# relay_isolation_circuit.net
KiCad netlist of a schematic drawn in Altium Designer
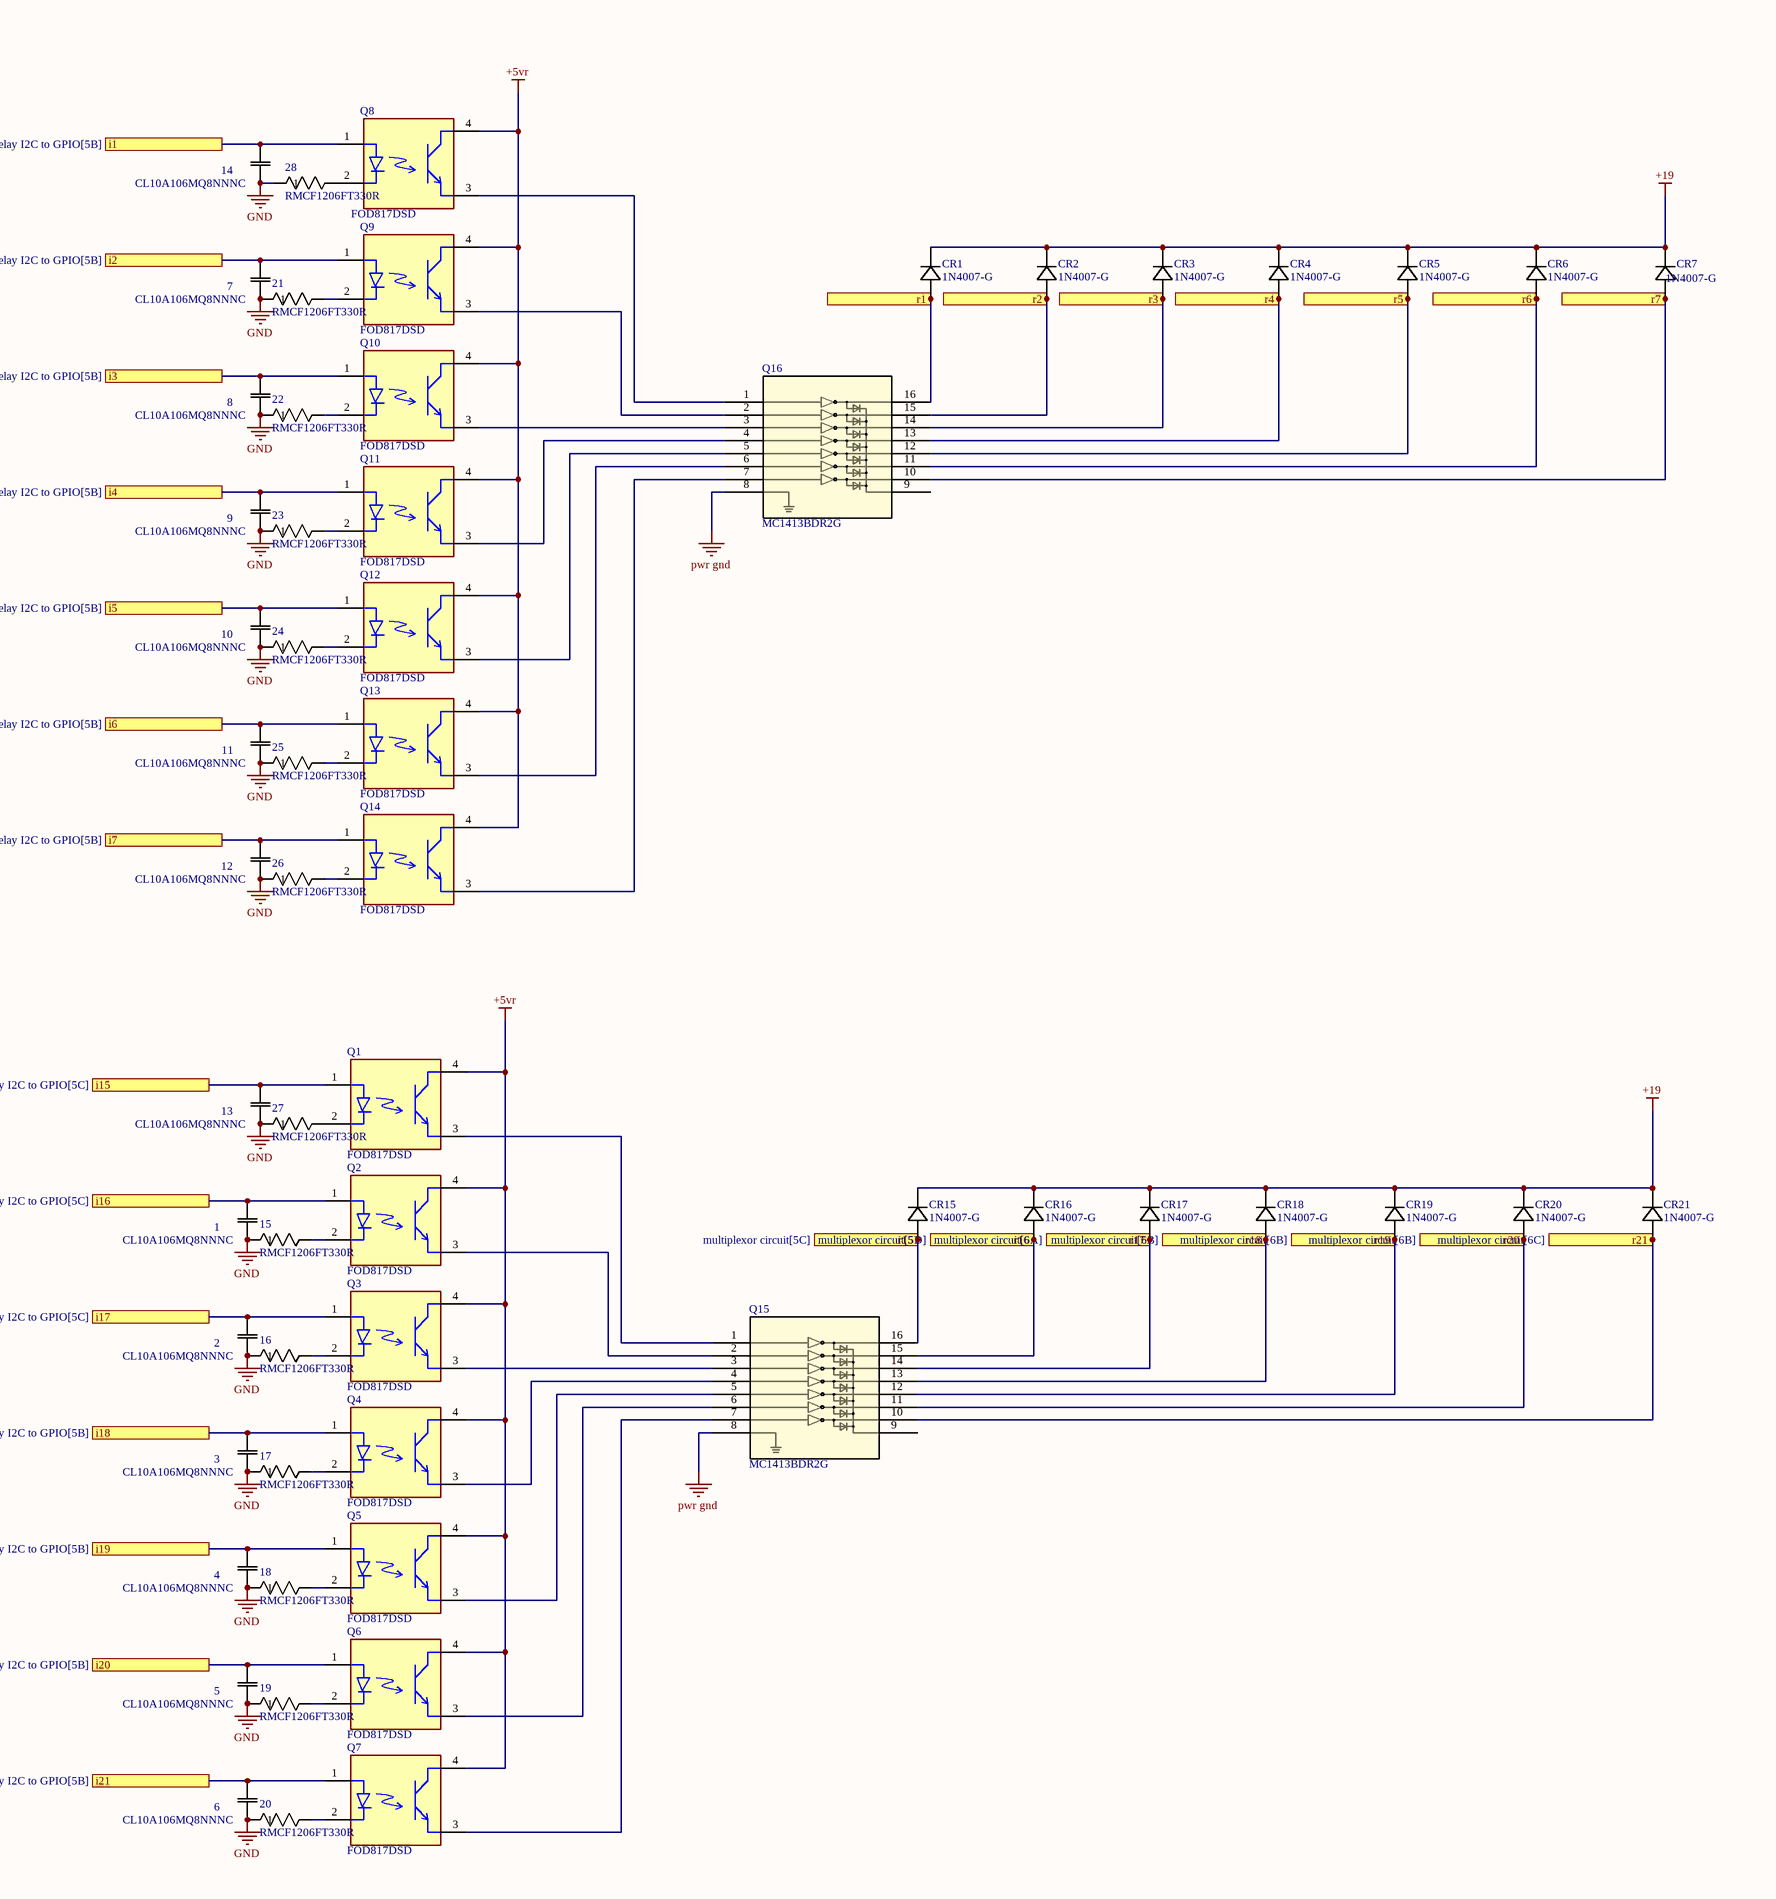
[diagram p0: relay isolation circuit.SchDoc, left]
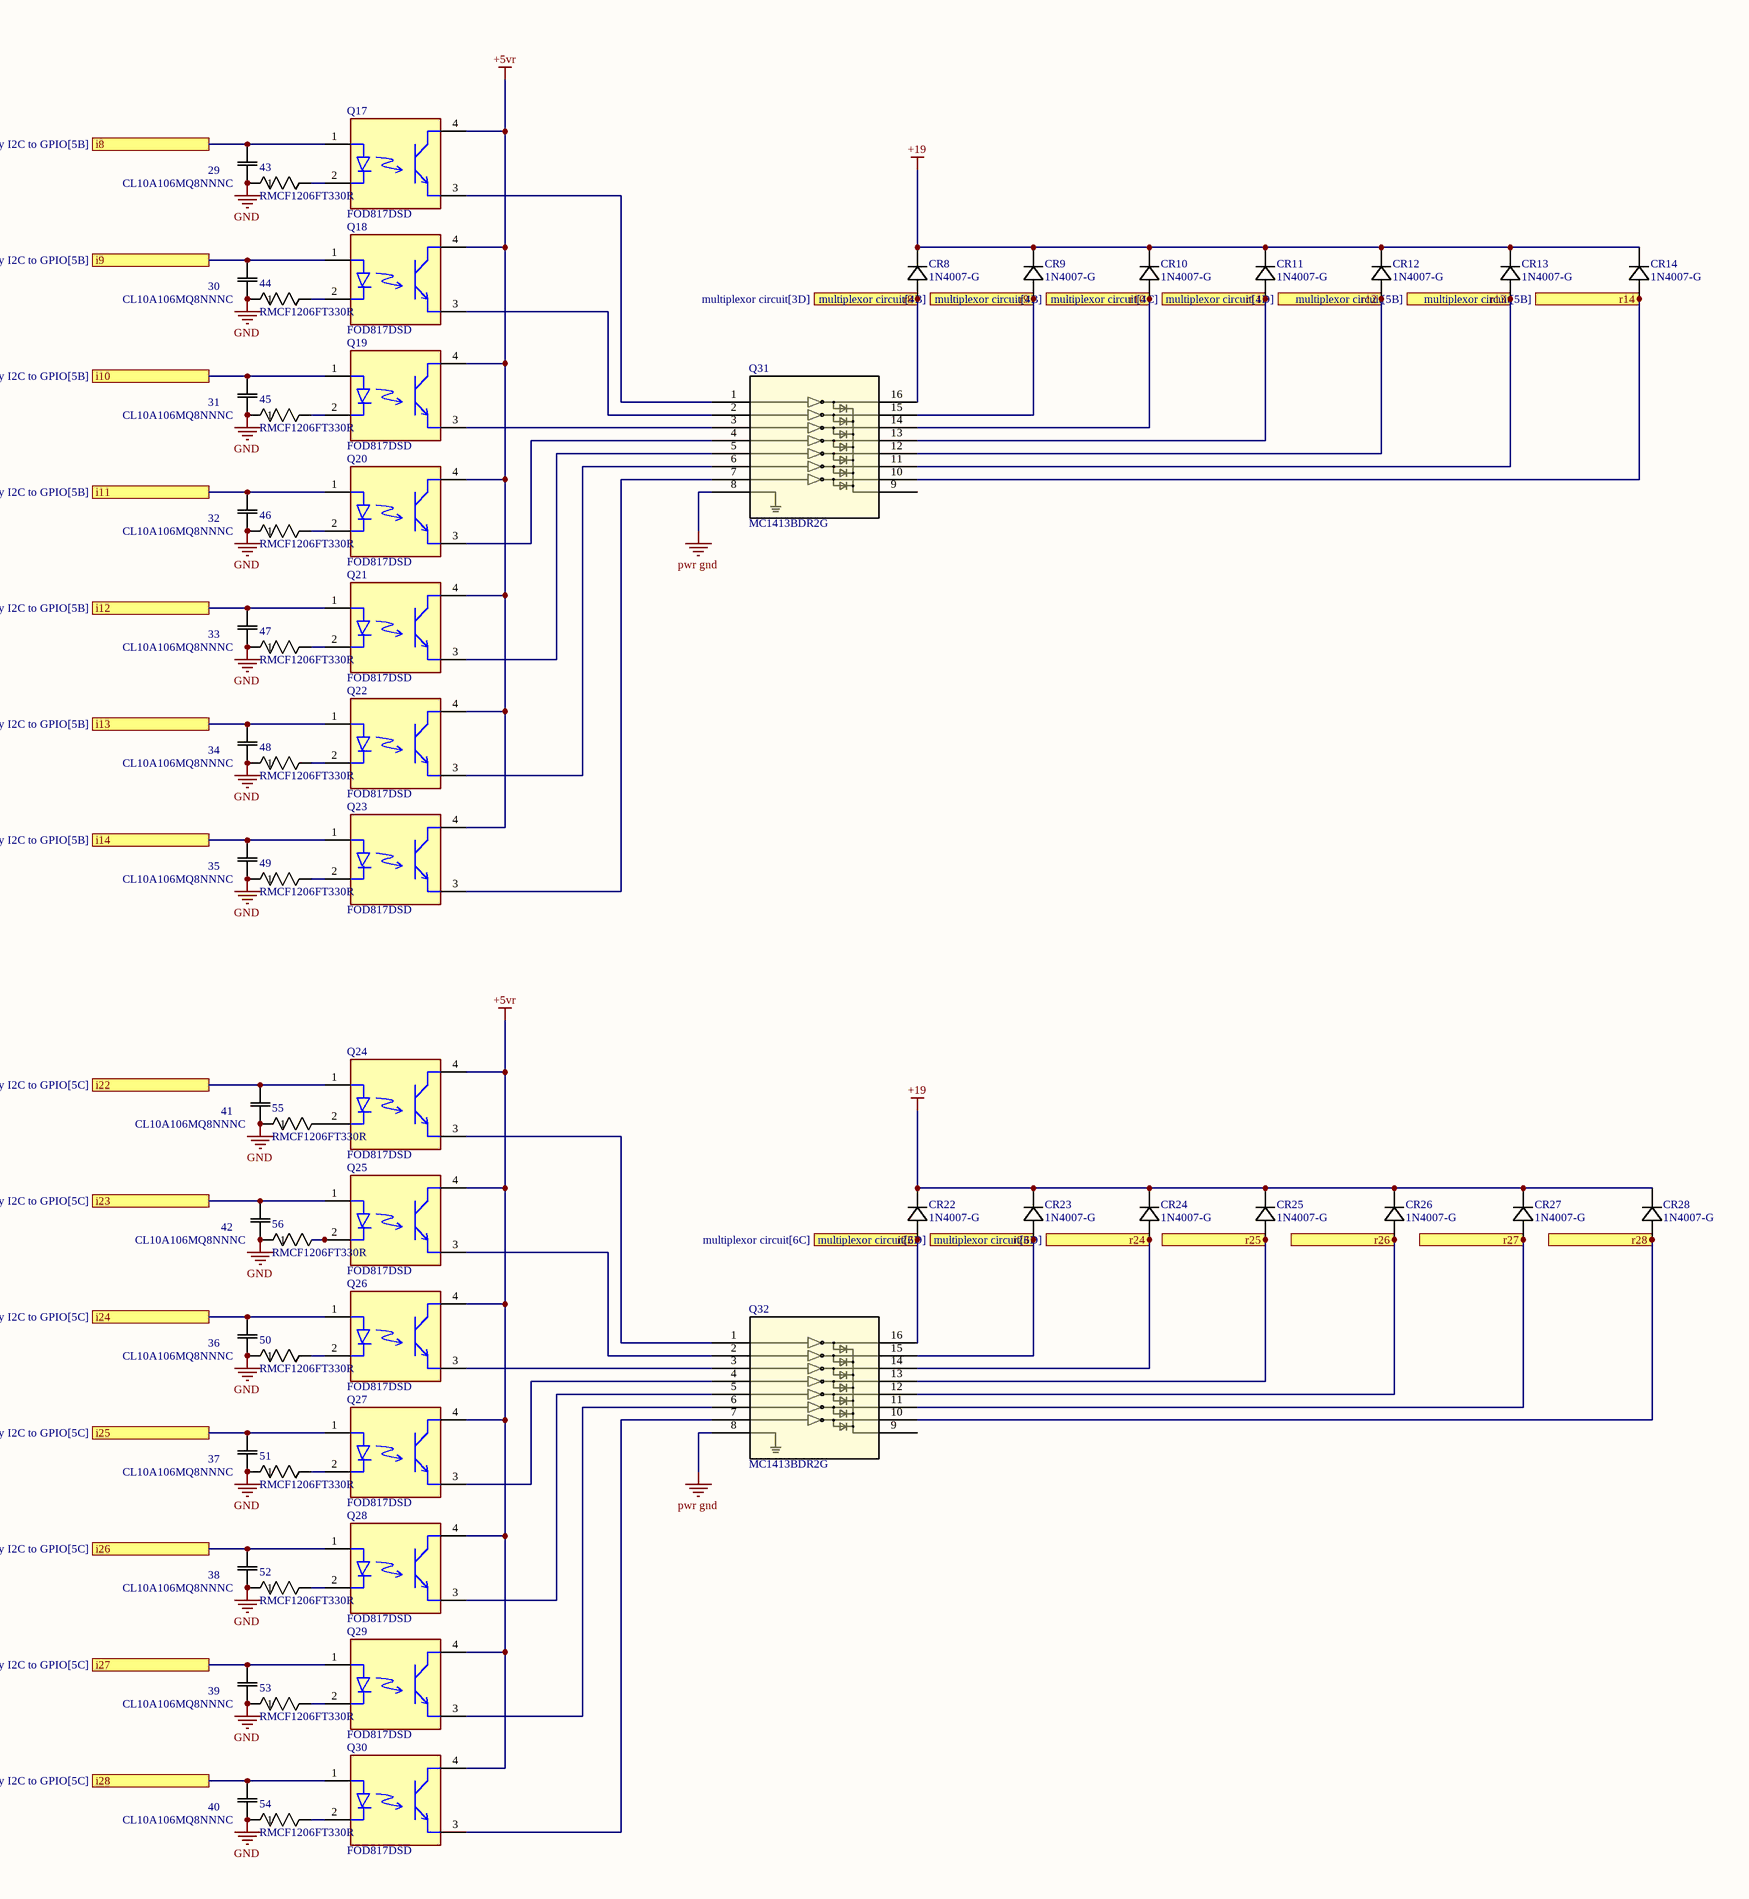
[diagram p1: relay isolation circuit.SchDoc, right]

(export (version "E")
  (design (tool "Eeschema 10.0.6"))
  (components
    (comp (ref "1")
      (value "CL10A106MQ8NNNC")
      (footprint "CAP_CL10_SAM")
      (description "No Description Available")
      (fields (field (name "COPYRIGHT") "Copyright (C) 2022 Ultra Librarian. All rights reserved."))
      (libsource (lib "CL10A106MQ8NNNC") (part "CL10A106MQ8NNNC"))
    )
    (comp (ref "2")
      (value "CL10A106MQ8NNNC")
      (footprint "CAP_CL10_SAM")
      (description "No Description Available")
      (fields (field (name "COPYRIGHT") "Copyright (C) 2022 Ultra Librarian. All rights reserved."))
      (libsource (lib "CL10A106MQ8NNNC") (part "CL10A106MQ8NNNC"))
    )
    (comp (ref "3")
      (value "CL10A106MQ8NNNC")
      (footprint "CAP_CL10_SAM")
      (description "No Description Available")
      (fields (field (name "COPYRIGHT") "Copyright (C) 2022 Ultra Librarian. All rights reserved."))
      (libsource (lib "CL10A106MQ8NNNC") (part "CL10A106MQ8NNNC"))
    )
    (comp (ref "4")
      (value "CL10A106MQ8NNNC")
      (footprint "CAP_CL10_SAM")
      (description "No Description Available")
      (fields (field (name "COPYRIGHT") "Copyright (C) 2022 Ultra Librarian. All rights reserved."))
      (libsource (lib "CL10A106MQ8NNNC") (part "CL10A106MQ8NNNC"))
    )
    (comp (ref "5")
      (value "CL10A106MQ8NNNC")
      (footprint "CAP_CL10_SAM")
      (description "No Description Available")
      (fields (field (name "COPYRIGHT") "Copyright (C) 2022 Ultra Librarian. All rights reserved."))
      (libsource (lib "CL10A106MQ8NNNC") (part "CL10A106MQ8NNNC"))
    )
    (comp (ref "6")
      (value "CL10A106MQ8NNNC")
      (footprint "CAP_CL10_SAM")
      (description "No Description Available")
      (fields (field (name "COPYRIGHT") "Copyright (C) 2022 Ultra Librarian. All rights reserved."))
      (libsource (lib "CL10A106MQ8NNNC") (part "CL10A106MQ8NNNC"))
    )
    (comp (ref "7")
      (value "CL10A106MQ8NNNC")
      (footprint "CAP_CL10_SAM")
      (description "No Description Available")
      (fields (field (name "COPYRIGHT") "Copyright (C) 2022 Ultra Librarian. All rights reserved."))
      (libsource (lib "CL10A106MQ8NNNC") (part "CL10A106MQ8NNNC"))
    )
    (comp (ref "8")
      (value "CL10A106MQ8NNNC")
      (footprint "CAP_CL10_SAM")
      (description "No Description Available")
      (fields (field (name "COPYRIGHT") "Copyright (C) 2022 Ultra Librarian. All rights reserved."))
      (libsource (lib "CL10A106MQ8NNNC") (part "CL10A106MQ8NNNC"))
    )
    (comp (ref "9")
      (value "CL10A106MQ8NNNC")
      (footprint "CAP_CL10_SAM")
      (description "No Description Available")
      (fields (field (name "COPYRIGHT") "Copyright (C) 2022 Ultra Librarian. All rights reserved."))
      (libsource (lib "CL10A106MQ8NNNC") (part "CL10A106MQ8NNNC"))
    )
    (comp (ref "10")
      (value "CL10A106MQ8NNNC")
      (footprint "CAP_CL10_SAM")
      (description "No Description Available")
      (fields (field (name "COPYRIGHT") "Copyright (C) 2022 Ultra Librarian. All rights reserved."))
      (libsource (lib "CL10A106MQ8NNNC") (part "CL10A106MQ8NNNC"))
    )
    (comp (ref "11")
      (value "CL10A106MQ8NNNC")
      (footprint "CAP_CL10_SAM")
      (description "No Description Available")
      (fields (field (name "COPYRIGHT") "Copyright (C) 2022 Ultra Librarian. All rights reserved."))
      (libsource (lib "CL10A106MQ8NNNC") (part "CL10A106MQ8NNNC"))
    )
    (comp (ref "12")
      (value "CL10A106MQ8NNNC")
      (footprint "CAP_CL10_SAM")
      (description "No Description Available")
      (fields (field (name "COPYRIGHT") "Copyright (C) 2022 Ultra Librarian. All rights reserved."))
      (libsource (lib "CL10A106MQ8NNNC") (part "CL10A106MQ8NNNC"))
    )
    (comp (ref "13")
      (value "CL10A106MQ8NNNC")
      (footprint "CAP_CL10_SAM")
      (description "No Description Available")
      (fields (field (name "COPYRIGHT") "Copyright (C) 2022 Ultra Librarian. All rights reserved."))
      (libsource (lib "CL10A106MQ8NNNC") (part "CL10A106MQ8NNNC"))
    )
    (comp (ref "14")
      (value "CL10A106MQ8NNNC")
      (footprint "CAP_CL10_SAM")
      (description "No Description Available")
      (fields (field (name "COPYRIGHT") "Copyright (C) 2022 Ultra Librarian. All rights reserved."))
      (libsource (lib "CL10A106MQ8NNNC") (part "CL10A106MQ8NNNC"))
    )
    (comp (ref "15")
      (value "RMCF1206FT330R")
      (footprint "STA_RMCF1206_STP")
      (description "No Description Available")
      (fields (field (name "COPYRIGHT") "Copyright (C) 2022 Ultra Librarian. All rights reserved."))
      (libsource (lib "RMCF1206FT330R") (part "RMCF1206FT330R"))
    )
    (comp (ref "16")
      (value "RMCF1206FT330R")
      (footprint "STA_RMCF1206_STP")
      (description "No Description Available")
      (fields (field (name "COPYRIGHT") "Copyright (C) 2022 Ultra Librarian. All rights reserved."))
      (libsource (lib "RMCF1206FT330R") (part "RMCF1206FT330R"))
    )
    (comp (ref "17")
      (value "RMCF1206FT330R")
      (footprint "STA_RMCF1206_STP")
      (description "No Description Available")
      (fields (field (name "COPYRIGHT") "Copyright (C) 2022 Ultra Librarian. All rights reserved."))
      (libsource (lib "RMCF1206FT330R") (part "RMCF1206FT330R"))
    )
    (comp (ref "18")
      (value "RMCF1206FT330R")
      (footprint "STA_RMCF1206_STP")
      (description "No Description Available")
      (fields (field (name "COPYRIGHT") "Copyright (C) 2022 Ultra Librarian. All rights reserved."))
      (libsource (lib "RMCF1206FT330R") (part "RMCF1206FT330R"))
    )
    (comp (ref "19")
      (value "RMCF1206FT330R")
      (footprint "STA_RMCF1206_STP")
      (description "No Description Available")
      (fields (field (name "COPYRIGHT") "Copyright (C) 2022 Ultra Librarian. All rights reserved."))
      (libsource (lib "RMCF1206FT330R") (part "RMCF1206FT330R"))
    )
    (comp (ref "20")
      (value "RMCF1206FT330R")
      (footprint "STA_RMCF1206_STP")
      (description "No Description Available")
      (fields (field (name "COPYRIGHT") "Copyright (C) 2022 Ultra Librarian. All rights reserved."))
      (libsource (lib "RMCF1206FT330R") (part "RMCF1206FT330R"))
    )
    (comp (ref "21")
      (value "RMCF1206FT330R")
      (footprint "STA_RMCF1206_STP")
      (description "No Description Available")
      (fields (field (name "COPYRIGHT") "Copyright (C) 2022 Ultra Librarian. All rights reserved."))
      (libsource (lib "RMCF1206FT330R") (part "RMCF1206FT330R"))
    )
    (comp (ref "22")
      (value "RMCF1206FT330R")
      (footprint "STA_RMCF1206_STP")
      (description "No Description Available")
      (fields (field (name "COPYRIGHT") "Copyright (C) 2022 Ultra Librarian. All rights reserved."))
      (libsource (lib "RMCF1206FT330R") (part "RMCF1206FT330R"))
    )
    (comp (ref "23")
      (value "RMCF1206FT330R")
      (footprint "STA_RMCF1206_STP")
      (description "No Description Available")
      (fields (field (name "COPYRIGHT") "Copyright (C) 2022 Ultra Librarian. All rights reserved."))
      (libsource (lib "RMCF1206FT330R") (part "RMCF1206FT330R"))
    )
    (comp (ref "24")
      (value "RMCF1206FT330R")
      (footprint "STA_RMCF1206_STP")
      (description "No Description Available")
      (fields (field (name "COPYRIGHT") "Copyright (C) 2022 Ultra Librarian. All rights reserved."))
      (libsource (lib "RMCF1206FT330R") (part "RMCF1206FT330R"))
    )
    (comp (ref "25")
      (value "RMCF1206FT330R")
      (footprint "STA_RMCF1206_STP")
      (description "No Description Available")
      (fields (field (name "COPYRIGHT") "Copyright (C) 2022 Ultra Librarian. All rights reserved."))
      (libsource (lib "RMCF1206FT330R") (part "RMCF1206FT330R"))
    )
    (comp (ref "26")
      (value "RMCF1206FT330R")
      (footprint "STA_RMCF1206_STP")
      (description "No Description Available")
      (fields (field (name "COPYRIGHT") "Copyright (C) 2022 Ultra Librarian. All rights reserved."))
      (libsource (lib "RMCF1206FT330R") (part "RMCF1206FT330R"))
    )
    (comp (ref "27")
      (value "RMCF1206FT330R")
      (footprint "STA_RMCF1206_STP")
      (description "No Description Available")
      (fields (field (name "COPYRIGHT") "Copyright (C) 2022 Ultra Librarian. All rights reserved."))
      (libsource (lib "RMCF1206FT330R") (part "RMCF1206FT330R"))
    )
    (comp (ref "28")
      (value "RMCF1206FT330R")
      (footprint "STA_RMCF1206_STP")
      (description "No Description Available")
      (fields (field (name "COPYRIGHT") "Copyright (C) 2022 Ultra Librarian. All rights reserved."))
      (libsource (lib "RMCF1206FT330R") (part "RMCF1206FT330R"))
    )
    (comp (ref "29")
      (value "CL10A106MQ8NNNC")
      (footprint "CAP_CL10_SAM")
      (description "No Description Available")
      (fields (field (name "COPYRIGHT") "Copyright (C) 2022 Ultra Librarian. All rights reserved."))
      (libsource (lib "CL10A106MQ8NNNC") (part "CL10A106MQ8NNNC"))
    )
    (comp (ref "30")
      (value "CL10A106MQ8NNNC")
      (footprint "CAP_CL10_SAM")
      (description "No Description Available")
      (fields (field (name "COPYRIGHT") "Copyright (C) 2022 Ultra Librarian. All rights reserved."))
      (libsource (lib "CL10A106MQ8NNNC") (part "CL10A106MQ8NNNC"))
    )
    (comp (ref "31")
      (value "CL10A106MQ8NNNC")
      (footprint "CAP_CL10_SAM")
      (description "No Description Available")
      (fields (field (name "COPYRIGHT") "Copyright (C) 2022 Ultra Librarian. All rights reserved."))
      (libsource (lib "CL10A106MQ8NNNC") (part "CL10A106MQ8NNNC"))
    )
    (comp (ref "32")
      (value "CL10A106MQ8NNNC")
      (footprint "CAP_CL10_SAM")
      (description "No Description Available")
      (fields (field (name "COPYRIGHT") "Copyright (C) 2022 Ultra Librarian. All rights reserved."))
      (libsource (lib "CL10A106MQ8NNNC") (part "CL10A106MQ8NNNC"))
    )
    (comp (ref "33")
      (value "CL10A106MQ8NNNC")
      (footprint "CAP_CL10_SAM")
      (description "No Description Available")
      (fields (field (name "COPYRIGHT") "Copyright (C) 2022 Ultra Librarian. All rights reserved."))
      (libsource (lib "CL10A106MQ8NNNC") (part "CL10A106MQ8NNNC"))
    )
    (comp (ref "34")
      (value "CL10A106MQ8NNNC")
      (footprint "CAP_CL10_SAM")
      (description "No Description Available")
      (fields (field (name "COPYRIGHT") "Copyright (C) 2022 Ultra Librarian. All rights reserved."))
      (libsource (lib "CL10A106MQ8NNNC") (part "CL10A106MQ8NNNC"))
    )
    (comp (ref "35")
      (value "CL10A106MQ8NNNC")
      (footprint "CAP_CL10_SAM")
      (description "No Description Available")
      (fields (field (name "COPYRIGHT") "Copyright (C) 2022 Ultra Librarian. All rights reserved."))
      (libsource (lib "CL10A106MQ8NNNC") (part "CL10A106MQ8NNNC"))
    )
    (comp (ref "36")
      (value "CL10A106MQ8NNNC")
      (footprint "CAP_CL10_SAM")
      (description "No Description Available")
      (fields (field (name "COPYRIGHT") "Copyright (C) 2022 Ultra Librarian. All rights reserved."))
      (libsource (lib "CL10A106MQ8NNNC") (part "CL10A106MQ8NNNC"))
    )
    (comp (ref "37")
      (value "CL10A106MQ8NNNC")
      (footprint "CAP_CL10_SAM")
      (description "No Description Available")
      (fields (field (name "COPYRIGHT") "Copyright (C) 2022 Ultra Librarian. All rights reserved."))
      (libsource (lib "CL10A106MQ8NNNC") (part "CL10A106MQ8NNNC"))
    )
    (comp (ref "38")
      (value "CL10A106MQ8NNNC")
      (footprint "CAP_CL10_SAM")
      (description "No Description Available")
      (fields (field (name "COPYRIGHT") "Copyright (C) 2022 Ultra Librarian. All rights reserved."))
      (libsource (lib "CL10A106MQ8NNNC") (part "CL10A106MQ8NNNC"))
    )
    (comp (ref "39")
      (value "CL10A106MQ8NNNC")
      (footprint "CAP_CL10_SAM")
      (description "No Description Available")
      (fields (field (name "COPYRIGHT") "Copyright (C) 2022 Ultra Librarian. All rights reserved."))
      (libsource (lib "CL10A106MQ8NNNC") (part "CL10A106MQ8NNNC"))
    )
    (comp (ref "40")
      (value "CL10A106MQ8NNNC")
      (footprint "CAP_CL10_SAM")
      (description "No Description Available")
      (fields (field (name "COPYRIGHT") "Copyright (C) 2022 Ultra Librarian. All rights reserved."))
      (libsource (lib "CL10A106MQ8NNNC") (part "CL10A106MQ8NNNC"))
    )
    (comp (ref "41")
      (value "CL10A106MQ8NNNC")
      (footprint "CAP_CL10_SAM")
      (description "No Description Available")
      (fields (field (name "COPYRIGHT") "Copyright (C) 2022 Ultra Librarian. All rights reserved."))
      (libsource (lib "CL10A106MQ8NNNC") (part "CL10A106MQ8NNNC"))
    )
    (comp (ref "42")
      (value "CL10A106MQ8NNNC")
      (footprint "CAP_CL10_SAM")
      (description "No Description Available")
      (fields (field (name "COPYRIGHT") "Copyright (C) 2022 Ultra Librarian. All rights reserved."))
      (libsource (lib "CL10A106MQ8NNNC") (part "CL10A106MQ8NNNC"))
    )
    (comp (ref "43")
      (value "RMCF1206FT330R")
      (footprint "STA_RMCF1206_STP")
      (description "No Description Available")
      (fields (field (name "COPYRIGHT") "Copyright (C) 2022 Ultra Librarian. All rights reserved."))
      (libsource (lib "RMCF1206FT330R") (part "RMCF1206FT330R"))
    )
    (comp (ref "44")
      (value "RMCF1206FT330R")
      (footprint "STA_RMCF1206_STP")
      (description "No Description Available")
      (fields (field (name "COPYRIGHT") "Copyright (C) 2022 Ultra Librarian. All rights reserved."))
      (libsource (lib "RMCF1206FT330R") (part "RMCF1206FT330R"))
    )
    (comp (ref "45")
      (value "RMCF1206FT330R")
      (footprint "STA_RMCF1206_STP")
      (description "No Description Available")
      (fields (field (name "COPYRIGHT") "Copyright (C) 2022 Ultra Librarian. All rights reserved."))
      (libsource (lib "RMCF1206FT330R") (part "RMCF1206FT330R"))
    )
    (comp (ref "46")
      (value "RMCF1206FT330R")
      (footprint "STA_RMCF1206_STP")
      (description "No Description Available")
      (fields (field (name "COPYRIGHT") "Copyright (C) 2022 Ultra Librarian. All rights reserved."))
      (libsource (lib "RMCF1206FT330R") (part "RMCF1206FT330R"))
    )
    (comp (ref "47")
      (value "RMCF1206FT330R")
      (footprint "STA_RMCF1206_STP")
      (description "No Description Available")
      (fields (field (name "COPYRIGHT") "Copyright (C) 2022 Ultra Librarian. All rights reserved."))
      (libsource (lib "RMCF1206FT330R") (part "RMCF1206FT330R"))
    )
    (comp (ref "48")
      (value "RMCF1206FT330R")
      (footprint "STA_RMCF1206_STP")
      (description "No Description Available")
      (fields (field (name "COPYRIGHT") "Copyright (C) 2022 Ultra Librarian. All rights reserved."))
      (libsource (lib "RMCF1206FT330R") (part "RMCF1206FT330R"))
    )
    (comp (ref "49")
      (value "RMCF1206FT330R")
      (footprint "STA_RMCF1206_STP")
      (description "No Description Available")
      (fields (field (name "COPYRIGHT") "Copyright (C) 2022 Ultra Librarian. All rights reserved."))
      (libsource (lib "RMCF1206FT330R") (part "RMCF1206FT330R"))
    )
    (comp (ref "50")
      (value "RMCF1206FT330R")
      (footprint "STA_RMCF1206_STP")
      (description "No Description Available")
      (fields (field (name "COPYRIGHT") "Copyright (C) 2022 Ultra Librarian. All rights reserved."))
      (libsource (lib "RMCF1206FT330R") (part "RMCF1206FT330R"))
    )
    (comp (ref "51")
      (value "RMCF1206FT330R")
      (footprint "STA_RMCF1206_STP")
      (description "No Description Available")
      (fields (field (name "COPYRIGHT") "Copyright (C) 2022 Ultra Librarian. All rights reserved."))
      (libsource (lib "RMCF1206FT330R") (part "RMCF1206FT330R"))
    )
    (comp (ref "52")
      (value "RMCF1206FT330R")
      (footprint "STA_RMCF1206_STP")
      (description "No Description Available")
      (fields (field (name "COPYRIGHT") "Copyright (C) 2022 Ultra Librarian. All rights reserved."))
      (libsource (lib "RMCF1206FT330R") (part "RMCF1206FT330R"))
    )
    (comp (ref "53")
      (value "RMCF1206FT330R")
      (footprint "STA_RMCF1206_STP")
      (description "No Description Available")
      (fields (field (name "COPYRIGHT") "Copyright (C) 2022 Ultra Librarian. All rights reserved."))
      (libsource (lib "RMCF1206FT330R") (part "RMCF1206FT330R"))
    )
    (comp (ref "54")
      (value "RMCF1206FT330R")
      (footprint "STA_RMCF1206_STP")
      (description "No Description Available")
      (fields (field (name "COPYRIGHT") "Copyright (C) 2022 Ultra Librarian. All rights reserved."))
      (libsource (lib "RMCF1206FT330R") (part "RMCF1206FT330R"))
    )
    (comp (ref "55")
      (value "RMCF1206FT330R")
      (footprint "STA_RMCF1206_STP")
      (description "No Description Available")
      (fields (field (name "COPYRIGHT") "Copyright (C) 2022 Ultra Librarian. All rights reserved."))
      (libsource (lib "RMCF1206FT330R") (part "RMCF1206FT330R"))
    )
    (comp (ref "56")
      (value "RMCF1206FT330R")
      (footprint "STA_RMCF1206_STP")
      (description "No Description Available")
      (fields (field (name "COPYRIGHT") "Copyright (C) 2022 Ultra Librarian. All rights reserved."))
      (libsource (lib "RMCF1206FT330R") (part "RMCF1206FT330R"))
    )
    (comp (ref "CR1")
      (value "1N4007-G")
      (footprint "1N4-G")
      (description "No Description Available")
      (fields (field (name "COPYRIGHT") "Copyright (C) 2022 Ultra Librarian. All rights reserved."))
      (libsource (lib "multiplexorparts") (part "1N4007-G"))
    )
    (comp (ref "CR2")
      (value "1N4007-G")
      (footprint "1N4-G")
      (description "No Description Available")
      (fields (field (name "COPYRIGHT") "Copyright (C) 2022 Ultra Librarian. All rights reserved."))
      (libsource (lib "multiplexorparts") (part "1N4007-G"))
    )
    (comp (ref "CR3")
      (value "1N4007-G")
      (footprint "1N4-G")
      (description "No Description Available")
      (fields (field (name "COPYRIGHT") "Copyright (C) 2022 Ultra Librarian. All rights reserved."))
      (libsource (lib "multiplexorparts") (part "1N4007-G"))
    )
    (comp (ref "CR4")
      (value "1N4007-G")
      (footprint "1N4-G")
      (description "No Description Available")
      (fields (field (name "COPYRIGHT") "Copyright (C) 2022 Ultra Librarian. All rights reserved."))
      (libsource (lib "multiplexorparts") (part "1N4007-G"))
    )
    (comp (ref "CR5")
      (value "1N4007-G")
      (footprint "1N4-G")
      (description "No Description Available")
      (fields (field (name "COPYRIGHT") "Copyright (C) 2022 Ultra Librarian. All rights reserved."))
      (libsource (lib "multiplexorparts") (part "1N4007-G"))
    )
    (comp (ref "CR6")
      (value "1N4007-G")
      (footprint "1N4-G")
      (description "No Description Available")
      (fields (field (name "COPYRIGHT") "Copyright (C) 2022 Ultra Librarian. All rights reserved."))
      (libsource (lib "multiplexorparts") (part "1N4007-G"))
    )
    (comp (ref "CR7")
      (value "1N4007-G")
      (footprint "1N4-G")
      (description "No Description Available")
      (fields (field (name "COPYRIGHT") "Copyright (C) 2022 Ultra Librarian. All rights reserved."))
      (libsource (lib "multiplexorparts") (part "1N4007-G"))
    )
    (comp (ref "CR8")
      (value "1N4007-G")
      (footprint "1N4-G")
      (description "No Description Available")
      (fields (field (name "COPYRIGHT") "Copyright (C) 2022 Ultra Librarian. All rights reserved."))
      (libsource (lib "multiplexorparts") (part "1N4007-G"))
    )
    (comp (ref "CR9")
      (value "1N4007-G")
      (footprint "1N4-G")
      (description "No Description Available")
      (fields (field (name "COPYRIGHT") "Copyright (C) 2022 Ultra Librarian. All rights reserved."))
      (libsource (lib "multiplexorparts") (part "1N4007-G"))
    )
    (comp (ref "CR10")
      (value "1N4007-G")
      (footprint "1N4-G")
      (description "No Description Available")
      (fields (field (name "COPYRIGHT") "Copyright (C) 2022 Ultra Librarian. All rights reserved."))
      (libsource (lib "multiplexorparts") (part "1N4007-G"))
    )
    (comp (ref "CR11")
      (value "1N4007-G")
      (footprint "1N4-G")
      (description "No Description Available")
      (fields (field (name "COPYRIGHT") "Copyright (C) 2022 Ultra Librarian. All rights reserved."))
      (libsource (lib "multiplexorparts") (part "1N4007-G"))
    )
    (comp (ref "CR12")
      (value "1N4007-G")
      (footprint "1N4-G")
      (description "No Description Available")
      (fields (field (name "COPYRIGHT") "Copyright (C) 2022 Ultra Librarian. All rights reserved."))
      (libsource (lib "multiplexorparts") (part "1N4007-G"))
    )
    (comp (ref "CR13")
      (value "1N4007-G")
      (footprint "1N4-G")
      (description "No Description Available")
      (fields (field (name "COPYRIGHT") "Copyright (C) 2022 Ultra Librarian. All rights reserved."))
      (libsource (lib "multiplexorparts") (part "1N4007-G"))
    )
    (comp (ref "CR14")
      (value "1N4007-G")
      (footprint "1N4-G")
      (description "No Description Available")
      (fields (field (name "COPYRIGHT") "Copyright (C) 2022 Ultra Librarian. All rights reserved."))
      (libsource (lib "multiplexorparts") (part "1N4007-G"))
    )
    (comp (ref "CR15")
      (value "1N4007-G")
      (footprint "1N4-G")
      (description "No Description Available")
      (fields (field (name "COPYRIGHT") "Copyright (C) 2022 Ultra Librarian. All rights reserved."))
      (libsource (lib "multiplexorparts") (part "1N4007-G"))
    )
    (comp (ref "CR16")
      (value "1N4007-G")
      (footprint "1N4-G")
      (description "No Description Available")
      (fields (field (name "COPYRIGHT") "Copyright (C) 2022 Ultra Librarian. All rights reserved."))
      (libsource (lib "multiplexorparts") (part "1N4007-G"))
    )
    (comp (ref "CR17")
      (value "1N4007-G")
      (footprint "1N4-G")
      (description "No Description Available")
      (fields (field (name "COPYRIGHT") "Copyright (C) 2022 Ultra Librarian. All rights reserved."))
      (libsource (lib "multiplexorparts") (part "1N4007-G"))
    )
    (comp (ref "CR18")
      (value "1N4007-G")
      (footprint "1N4-G")
      (description "No Description Available")
      (fields (field (name "COPYRIGHT") "Copyright (C) 2022 Ultra Librarian. All rights reserved."))
      (libsource (lib "multiplexorparts") (part "1N4007-G"))
    )
    (comp (ref "CR19")
      (value "1N4007-G")
      (footprint "1N4-G")
      (description "No Description Available")
      (fields (field (name "COPYRIGHT") "Copyright (C) 2022 Ultra Librarian. All rights reserved."))
      (libsource (lib "multiplexorparts") (part "1N4007-G"))
    )
    (comp (ref "CR20")
      (value "1N4007-G")
      (footprint "1N4-G")
      (description "No Description Available")
      (fields (field (name "COPYRIGHT") "Copyright (C) 2022 Ultra Librarian. All rights reserved."))
      (libsource (lib "multiplexorparts") (part "1N4007-G"))
    )
    (comp (ref "CR21")
      (value "1N4007-G")
      (footprint "1N4-G")
      (description "No Description Available")
      (fields (field (name "COPYRIGHT") "Copyright (C) 2022 Ultra Librarian. All rights reserved."))
      (libsource (lib "multiplexorparts") (part "1N4007-G"))
    )
    (comp (ref "CR22")
      (value "1N4007-G")
      (footprint "1N4-G")
      (description "No Description Available")
      (fields (field (name "COPYRIGHT") "Copyright (C) 2022 Ultra Librarian. All rights reserved."))
      (libsource (lib "multiplexorparts") (part "1N4007-G"))
    )
    (comp (ref "CR23")
      (value "1N4007-G")
      (footprint "1N4-G")
      (description "No Description Available")
      (fields (field (name "COPYRIGHT") "Copyright (C) 2022 Ultra Librarian. All rights reserved."))
      (libsource (lib "multiplexorparts") (part "1N4007-G"))
    )
    (comp (ref "CR24")
      (value "1N4007-G")
      (footprint "1N4-G")
      (description "No Description Available")
      (fields (field (name "COPYRIGHT") "Copyright (C) 2022 Ultra Librarian. All rights reserved."))
      (libsource (lib "multiplexorparts") (part "1N4007-G"))
    )
    (comp (ref "CR25")
      (value "1N4007-G")
      (footprint "1N4-G")
      (description "No Description Available")
      (fields (field (name "COPYRIGHT") "Copyright (C) 2022 Ultra Librarian. All rights reserved."))
      (libsource (lib "multiplexorparts") (part "1N4007-G"))
    )
    (comp (ref "CR26")
      (value "1N4007-G")
      (footprint "1N4-G")
      (description "No Description Available")
      (fields (field (name "COPYRIGHT") "Copyright (C) 2022 Ultra Librarian. All rights reserved."))
      (libsource (lib "multiplexorparts") (part "1N4007-G"))
    )
    (comp (ref "CR27")
      (value "1N4007-G")
      (footprint "1N4-G")
      (description "No Description Available")
      (fields (field (name "COPYRIGHT") "Copyright (C) 2022 Ultra Librarian. All rights reserved."))
      (libsource (lib "multiplexorparts") (part "1N4007-G"))
    )
    (comp (ref "CR28")
      (value "1N4007-G")
      (footprint "1N4-G")
      (description "No Description Available")
      (fields (field (name "COPYRIGHT") "Copyright (C) 2022 Ultra Librarian. All rights reserved."))
      (libsource (lib "multiplexorparts") (part "1N4007-G"))
    )
    (comp (ref "Q1")
      (value "FOD817DSD")
      (footprint "FP-709AH-MFG")
      (description "OPTOISOLATOR 5KV TRANSISTOR 4SMD")
      (fields
        (field (name "MANUFACTURER") "ON Semiconductor")
        (field (name "OCTOPART") "https://octopart.com/fod817dsd-on+semiconductor-84327554")
      )
      (libsource (lib "Altium Content Vault") (part "d722738cb024cbb2b7d208cd16f279d"))
    )
    (comp (ref "Q2")
      (value "FOD817DSD")
      (footprint "FP-709AH-MFG")
      (description "OPTOISOLATOR 5KV TRANSISTOR 4SMD")
      (fields
        (field (name "MANUFACTURER") "ON Semiconductor")
        (field (name "OCTOPART") "https://octopart.com/fod817dsd-on+semiconductor-84327554")
      )
      (libsource (lib "Altium Content Vault") (part "d722738cb024cbb2b7d208cd16f279d"))
    )
    (comp (ref "Q3")
      (value "FOD817DSD")
      (footprint "FP-709AH-MFG")
      (description "OPTOISOLATOR 5KV TRANSISTOR 4SMD")
      (fields
        (field (name "MANUFACTURER") "ON Semiconductor")
        (field (name "OCTOPART") "https://octopart.com/fod817dsd-on+semiconductor-84327554")
      )
      (libsource (lib "Altium Content Vault") (part "d722738cb024cbb2b7d208cd16f279d"))
    )
    (comp (ref "Q4")
      (value "FOD817DSD")
      (footprint "FP-709AH-MFG")
      (description "OPTOISOLATOR 5KV TRANSISTOR 4SMD")
      (fields
        (field (name "MANUFACTURER") "ON Semiconductor")
        (field (name "OCTOPART") "https://octopart.com/fod817dsd-on+semiconductor-84327554")
      )
      (libsource (lib "Altium Content Vault") (part "d722738cb024cbb2b7d208cd16f279d"))
    )
    (comp (ref "Q5")
      (value "FOD817DSD")
      (footprint "FP-709AH-MFG")
      (description "OPTOISOLATOR 5KV TRANSISTOR 4SMD")
      (fields
        (field (name "MANUFACTURER") "ON Semiconductor")
        (field (name "OCTOPART") "https://octopart.com/fod817dsd-on+semiconductor-84327554")
      )
      (libsource (lib "Altium Content Vault") (part "d722738cb024cbb2b7d208cd16f279d"))
    )
    (comp (ref "Q6")
      (value "FOD817DSD")
      (footprint "FP-709AH-MFG")
      (description "OPTOISOLATOR 5KV TRANSISTOR 4SMD")
      (fields
        (field (name "MANUFACTURER") "ON Semiconductor")
        (field (name "OCTOPART") "https://octopart.com/fod817dsd-on+semiconductor-84327554")
      )
      (libsource (lib "Altium Content Vault") (part "d722738cb024cbb2b7d208cd16f279d"))
    )
    (comp (ref "Q7")
      (value "FOD817DSD")
      (footprint "FP-709AH-MFG")
      (description "OPTOISOLATOR 5KV TRANSISTOR 4SMD")
      (fields
        (field (name "MANUFACTURER") "ON Semiconductor")
        (field (name "OCTOPART") "https://octopart.com/fod817dsd-on+semiconductor-84327554")
      )
      (libsource (lib "Altium Content Vault") (part "d722738cb024cbb2b7d208cd16f279d"))
    )
    (comp (ref "Q8")
      (value "FOD817DSD")
      (footprint "FP-709AH-MFG")
      (description "OPTOISOLATOR 5KV TRANSISTOR 4SMD")
      (fields
        (field (name "MANUFACTURER") "ON Semiconductor")
        (field (name "OCTOPART") "https://octopart.com/fod817dsd-on+semiconductor-84327554")
      )
      (libsource (lib "Altium Content Vault") (part "d722738cb024cbb2b7d208cd16f279d"))
    )
    (comp (ref "Q9")
      (value "FOD817DSD")
      (footprint "FP-709AH-MFG")
      (description "OPTOISOLATOR 5KV TRANSISTOR 4SMD")
      (fields
        (field (name "MANUFACTURER") "ON Semiconductor")
        (field (name "OCTOPART") "https://octopart.com/fod817dsd-on+semiconductor-84327554")
      )
      (libsource (lib "Altium Content Vault") (part "d722738cb024cbb2b7d208cd16f279d"))
    )
    (comp (ref "Q10")
      (value "FOD817DSD")
      (footprint "FP-709AH-MFG")
      (description "OPTOISOLATOR 5KV TRANSISTOR 4SMD")
      (fields
        (field (name "MANUFACTURER") "ON Semiconductor")
        (field (name "OCTOPART") "https://octopart.com/fod817dsd-on+semiconductor-84327554")
      )
      (libsource (lib "Altium Content Vault") (part "d722738cb024cbb2b7d208cd16f279d"))
    )
    (comp (ref "Q11")
      (value "FOD817DSD")
      (footprint "FP-709AH-MFG")
      (description "OPTOISOLATOR 5KV TRANSISTOR 4SMD")
      (fields
        (field (name "MANUFACTURER") "ON Semiconductor")
        (field (name "OCTOPART") "https://octopart.com/fod817dsd-on+semiconductor-84327554")
      )
      (libsource (lib "Altium Content Vault") (part "d722738cb024cbb2b7d208cd16f279d"))
    )
    (comp (ref "Q12")
      (value "FOD817DSD")
      (footprint "FP-709AH-MFG")
      (description "OPTOISOLATOR 5KV TRANSISTOR 4SMD")
      (fields
        (field (name "MANUFACTURER") "ON Semiconductor")
        (field (name "OCTOPART") "https://octopart.com/fod817dsd-on+semiconductor-84327554")
      )
      (libsource (lib "Altium Content Vault") (part "d722738cb024cbb2b7d208cd16f279d"))
    )
    (comp (ref "Q13")
      (value "FOD817DSD")
      (footprint "FP-709AH-MFG")
      (description "OPTOISOLATOR 5KV TRANSISTOR 4SMD")
      (fields
        (field (name "MANUFACTURER") "ON Semiconductor")
        (field (name "OCTOPART") "https://octopart.com/fod817dsd-on+semiconductor-84327554")
      )
      (libsource (lib "Altium Content Vault") (part "d722738cb024cbb2b7d208cd16f279d"))
    )
    (comp (ref "Q14")
      (value "FOD817DSD")
      (footprint "FP-709AH-MFG")
      (description "OPTOISOLATOR 5KV TRANSISTOR 4SMD")
      (fields
        (field (name "MANUFACTURER") "ON Semiconductor")
        (field (name "OCTOPART") "https://octopart.com/fod817dsd-on+semiconductor-84327554")
      )
      (libsource (lib "Altium Content Vault") (part "d722738cb024cbb2b7d208cd16f279d"))
    )
    (comp (ref "Q15")
      (value "MC1413BDR2G")
      (footprint "SOIC16_751B-05_ONS")
      (description "No Description Available")
      (fields (field (name "COPYRIGHT") "Copyright (C) 2022 Ultra Librarian. All rights reserved."))
      (libsource (lib "MC1413BDR2G") (part "MC1413BDR2G"))
    )
    (comp (ref "Q16")
      (value "MC1413BDR2G")
      (footprint "SOIC16_751B-05_ONS")
      (description "No Description Available")
      (fields (field (name "COPYRIGHT") "Copyright (C) 2022 Ultra Librarian. All rights reserved."))
      (libsource (lib "MC1413BDR2G") (part "MC1413BDR2G"))
    )
    (comp (ref "Q17")
      (value "FOD817DSD")
      (footprint "FP-709AH-MFG")
      (description "OPTOISOLATOR 5KV TRANSISTOR 4SMD")
      (fields
        (field (name "MANUFACTURER") "ON Semiconductor")
        (field (name "OCTOPART") "https://octopart.com/fod817dsd-on+semiconductor-84327554")
      )
      (libsource (lib "Altium Content Vault") (part "d722738cb024cbb2b7d208cd16f279d"))
    )
    (comp (ref "Q18")
      (value "FOD817DSD")
      (footprint "FP-709AH-MFG")
      (description "OPTOISOLATOR 5KV TRANSISTOR 4SMD")
      (fields
        (field (name "MANUFACTURER") "ON Semiconductor")
        (field (name "OCTOPART") "https://octopart.com/fod817dsd-on+semiconductor-84327554")
      )
      (libsource (lib "Altium Content Vault") (part "d722738cb024cbb2b7d208cd16f279d"))
    )
    (comp (ref "Q19")
      (value "FOD817DSD")
      (footprint "FP-709AH-MFG")
      (description "OPTOISOLATOR 5KV TRANSISTOR 4SMD")
      (fields
        (field (name "MANUFACTURER") "ON Semiconductor")
        (field (name "OCTOPART") "https://octopart.com/fod817dsd-on+semiconductor-84327554")
      )
      (libsource (lib "Altium Content Vault") (part "d722738cb024cbb2b7d208cd16f279d"))
    )
    (comp (ref "Q20")
      (value "FOD817DSD")
      (footprint "FP-709AH-MFG")
      (description "OPTOISOLATOR 5KV TRANSISTOR 4SMD")
      (fields
        (field (name "MANUFACTURER") "ON Semiconductor")
        (field (name "OCTOPART") "https://octopart.com/fod817dsd-on+semiconductor-84327554")
      )
      (libsource (lib "Altium Content Vault") (part "d722738cb024cbb2b7d208cd16f279d"))
    )
    (comp (ref "Q21")
      (value "FOD817DSD")
      (footprint "FP-709AH-MFG")
      (description "OPTOISOLATOR 5KV TRANSISTOR 4SMD")
      (fields
        (field (name "MANUFACTURER") "ON Semiconductor")
        (field (name "OCTOPART") "https://octopart.com/fod817dsd-on+semiconductor-84327554")
      )
      (libsource (lib "Altium Content Vault") (part "d722738cb024cbb2b7d208cd16f279d"))
    )
    (comp (ref "Q22")
      (value "FOD817DSD")
      (footprint "FP-709AH-MFG")
      (description "OPTOISOLATOR 5KV TRANSISTOR 4SMD")
      (fields
        (field (name "MANUFACTURER") "ON Semiconductor")
        (field (name "OCTOPART") "https://octopart.com/fod817dsd-on+semiconductor-84327554")
      )
      (libsource (lib "Altium Content Vault") (part "d722738cb024cbb2b7d208cd16f279d"))
    )
    (comp (ref "Q23")
      (value "FOD817DSD")
      (footprint "FP-709AH-MFG")
      (description "OPTOISOLATOR 5KV TRANSISTOR 4SMD")
      (fields
        (field (name "MANUFACTURER") "ON Semiconductor")
        (field (name "OCTOPART") "https://octopart.com/fod817dsd-on+semiconductor-84327554")
      )
      (libsource (lib "Altium Content Vault") (part "d722738cb024cbb2b7d208cd16f279d"))
    )
    (comp (ref "Q24")
      (value "FOD817DSD")
      (footprint "FP-709AH-MFG")
      (description "OPTOISOLATOR 5KV TRANSISTOR 4SMD")
      (fields
        (field (name "MANUFACTURER") "ON Semiconductor")
        (field (name "OCTOPART") "https://octopart.com/fod817dsd-on+semiconductor-84327554")
      )
      (libsource (lib "Altium Content Vault") (part "d722738cb024cbb2b7d208cd16f279d"))
    )
    (comp (ref "Q25")
      (value "FOD817DSD")
      (footprint "FP-709AH-MFG")
      (description "OPTOISOLATOR 5KV TRANSISTOR 4SMD")
      (fields
        (field (name "MANUFACTURER") "ON Semiconductor")
        (field (name "OCTOPART") "https://octopart.com/fod817dsd-on+semiconductor-84327554")
      )
      (libsource (lib "Altium Content Vault") (part "d722738cb024cbb2b7d208cd16f279d"))
    )
    (comp (ref "Q26")
      (value "FOD817DSD")
      (footprint "FP-709AH-MFG")
      (description "OPTOISOLATOR 5KV TRANSISTOR 4SMD")
      (fields
        (field (name "MANUFACTURER") "ON Semiconductor")
        (field (name "OCTOPART") "https://octopart.com/fod817dsd-on+semiconductor-84327554")
      )
      (libsource (lib "Altium Content Vault") (part "d722738cb024cbb2b7d208cd16f279d"))
    )
    (comp (ref "Q27")
      (value "FOD817DSD")
      (footprint "FP-709AH-MFG")
      (description "OPTOISOLATOR 5KV TRANSISTOR 4SMD")
      (fields
        (field (name "MANUFACTURER") "ON Semiconductor")
        (field (name "OCTOPART") "https://octopart.com/fod817dsd-on+semiconductor-84327554")
      )
      (libsource (lib "Altium Content Vault") (part "d722738cb024cbb2b7d208cd16f279d"))
    )
    (comp (ref "Q28")
      (value "FOD817DSD")
      (footprint "FP-709AH-MFG")
      (description "OPTOISOLATOR 5KV TRANSISTOR 4SMD")
      (fields
        (field (name "MANUFACTURER") "ON Semiconductor")
        (field (name "OCTOPART") "https://octopart.com/fod817dsd-on+semiconductor-84327554")
      )
      (libsource (lib "Altium Content Vault") (part "d722738cb024cbb2b7d208cd16f279d"))
    )
    (comp (ref "Q29")
      (value "FOD817DSD")
      (footprint "FP-709AH-MFG")
      (description "OPTOISOLATOR 5KV TRANSISTOR 4SMD")
      (fields
        (field (name "MANUFACTURER") "ON Semiconductor")
        (field (name "OCTOPART") "https://octopart.com/fod817dsd-on+semiconductor-84327554")
      )
      (libsource (lib "Altium Content Vault") (part "d722738cb024cbb2b7d208cd16f279d"))
    )
    (comp (ref "Q30")
      (value "FOD817DSD")
      (footprint "FP-709AH-MFG")
      (description "OPTOISOLATOR 5KV TRANSISTOR 4SMD")
      (fields
        (field (name "MANUFACTURER") "ON Semiconductor")
        (field (name "OCTOPART") "https://octopart.com/fod817dsd-on+semiconductor-84327554")
      )
      (libsource (lib "Altium Content Vault") (part "d722738cb024cbb2b7d208cd16f279d"))
    )
    (comp (ref "Q31")
      (value "MC1413BDR2G")
      (footprint "SOIC16_751B-05_ONS")
      (description "No Description Available")
      (fields (field (name "COPYRIGHT") "Copyright (C) 2022 Ultra Librarian. All rights reserved."))
      (libsource (lib "MC1413BDR2G") (part "MC1413BDR2G"))
    )
    (comp (ref "Q32")
      (value "MC1413BDR2G")
      (footprint "SOIC16_751B-05_ONS")
      (description "No Description Available")
      (fields (field (name "COPYRIGHT") "Copyright (C) 2022 Ultra Librarian. All rights reserved."))
      (libsource (lib "MC1413BDR2G") (part "MC1413BDR2G"))
    )
  )
  (nets
    (net (code "1") (name "+5vr") (class "Default")
      (node (ref "Q1") (pin "4") (pinfunction "C_4") (pintype "passive"))
      (node (ref "Q10") (pin "4") (pinfunction "C_4") (pintype "passive"))
      (node (ref "Q11") (pin "4") (pinfunction "C_4") (pintype "passive"))
      (node (ref "Q12") (pin "4") (pinfunction "C_4") (pintype "passive"))
      (node (ref "Q13") (pin "4") (pinfunction "C_4") (pintype "passive"))
      (node (ref "Q14") (pin "4") (pinfunction "C_4") (pintype "passive"))
      (node (ref "Q17") (pin "4") (pinfunction "C_4") (pintype "passive"))
      (node (ref "Q18") (pin "4") (pinfunction "C_4") (pintype "passive"))
      (node (ref "Q19") (pin "4") (pinfunction "C_4") (pintype "passive"))
      (node (ref "Q2") (pin "4") (pinfunction "C_4") (pintype "passive"))
      (node (ref "Q20") (pin "4") (pinfunction "C_4") (pintype "passive"))
      (node (ref "Q21") (pin "4") (pinfunction "C_4") (pintype "passive"))
      (node (ref "Q22") (pin "4") (pinfunction "C_4") (pintype "passive"))
      (node (ref "Q23") (pin "4") (pinfunction "C_4") (pintype "passive"))
      (node (ref "Q24") (pin "4") (pinfunction "C_4") (pintype "passive"))
      (node (ref "Q25") (pin "4") (pinfunction "C_4") (pintype "passive"))
      (node (ref "Q26") (pin "4") (pinfunction "C_4") (pintype "passive"))
      (node (ref "Q27") (pin "4") (pinfunction "C_4") (pintype "passive"))
      (node (ref "Q28") (pin "4") (pinfunction "C_4") (pintype "passive"))
      (node (ref "Q29") (pin "4") (pinfunction "C_4") (pintype "passive"))
      (node (ref "Q3") (pin "4") (pinfunction "C_4") (pintype "passive"))
      (node (ref "Q30") (pin "4") (pinfunction "C_4") (pintype "passive"))
      (node (ref "Q4") (pin "4") (pinfunction "C_4") (pintype "passive"))
      (node (ref "Q5") (pin "4") (pinfunction "C_4") (pintype "passive"))
      (node (ref "Q6") (pin "4") (pinfunction "C_4") (pintype "passive"))
      (node (ref "Q7") (pin "4") (pinfunction "C_4") (pintype "passive"))
      (node (ref "Q8") (pin "4") (pinfunction "C_4") (pintype "passive"))
      (node (ref "Q9") (pin "4") (pinfunction "C_4") (pintype "passive"))
    )
    (net (code "2") (name "+19") (class "Default")
      (node (ref "CR1") (pin "1") (pinfunction "11_1") (pintype "passive"))
      (node (ref "CR10") (pin "1") (pinfunction "11_1") (pintype "passive"))
      (node (ref "CR11") (pin "1") (pinfunction "11_1") (pintype "passive"))
      (node (ref "CR12") (pin "1") (pinfunction "11_1") (pintype "passive"))
      (node (ref "CR13") (pin "1") (pinfunction "11_1") (pintype "passive"))
      (node (ref "CR14") (pin "1") (pinfunction "11_1") (pintype "passive"))
      (node (ref "CR15") (pin "1") (pinfunction "11_1") (pintype "passive"))
      (node (ref "CR16") (pin "1") (pinfunction "11_1") (pintype "passive"))
      (node (ref "CR17") (pin "1") (pinfunction "11_1") (pintype "passive"))
      (node (ref "CR18") (pin "1") (pinfunction "11_1") (pintype "passive"))
      (node (ref "CR19") (pin "1") (pinfunction "11_1") (pintype "passive"))
      (node (ref "CR2") (pin "1") (pinfunction "11_1") (pintype "passive"))
      (node (ref "CR20") (pin "1") (pinfunction "11_1") (pintype "passive"))
      (node (ref "CR21") (pin "1") (pinfunction "11_1") (pintype "passive"))
      (node (ref "CR22") (pin "1") (pinfunction "11_1") (pintype "passive"))
      (node (ref "CR23") (pin "1") (pinfunction "11_1") (pintype "passive"))
      (node (ref "CR24") (pin "1") (pinfunction "11_1") (pintype "passive"))
      (node (ref "CR25") (pin "1") (pinfunction "11_1") (pintype "passive"))
      (node (ref "CR26") (pin "1") (pinfunction "11_1") (pintype "passive"))
      (node (ref "CR27") (pin "1") (pinfunction "11_1") (pintype "passive"))
      (node (ref "CR28") (pin "1") (pinfunction "11_1") (pintype "passive"))
      (node (ref "CR3") (pin "1") (pinfunction "11_1") (pintype "passive"))
      (node (ref "CR4") (pin "1") (pinfunction "11_1") (pintype "passive"))
      (node (ref "CR5") (pin "1") (pinfunction "11_1") (pintype "passive"))
      (node (ref "CR6") (pin "1") (pinfunction "11_1") (pintype "passive"))
      (node (ref "CR7") (pin "1") (pinfunction "11_1") (pintype "passive"))
      (node (ref "CR8") (pin "1") (pinfunction "11_1") (pintype "passive"))
      (node (ref "CR9") (pin "1") (pinfunction "11_1") (pintype "passive"))
    )
    (net (code "3") (name "/i1") (class "Default")
      (node (ref "14") (pin "2") (pinfunction "2_2") (pintype "passive"))
      (node (ref "Q8") (pin "1") (pinfunction "A_1") (pintype "passive"))
    )
    (net (code "4") (name "/i2") (class "Default")
      (node (ref "7") (pin "2") (pinfunction "2_2") (pintype "passive"))
      (node (ref "Q9") (pin "1") (pinfunction "A_1") (pintype "passive"))
    )
    (net (code "5") (name "/i3") (class "Default")
      (node (ref "8") (pin "2") (pinfunction "2_2") (pintype "passive"))
      (node (ref "Q10") (pin "1") (pinfunction "A_1") (pintype "passive"))
    )
    (net (code "6") (name "/i4") (class "Default")
      (node (ref "9") (pin "2") (pinfunction "2_2") (pintype "passive"))
      (node (ref "Q11") (pin "1") (pinfunction "A_1") (pintype "passive"))
    )
    (net (code "7") (name "/i5") (class "Default")
      (node (ref "10") (pin "2") (pinfunction "2_2") (pintype "passive"))
      (node (ref "Q12") (pin "1") (pinfunction "A_1") (pintype "passive"))
    )
    (net (code "8") (name "/i6") (class "Default")
      (node (ref "11") (pin "2") (pinfunction "2_2") (pintype "passive"))
      (node (ref "Q13") (pin "1") (pinfunction "A_1") (pintype "passive"))
    )
    (net (code "9") (name "/i7") (class "Default")
      (node (ref "12") (pin "2") (pinfunction "2_2") (pintype "passive"))
      (node (ref "Q14") (pin "1") (pinfunction "A_1") (pintype "passive"))
    )
    (net (code "10") (name "/i8") (class "Default")
      (node (ref "29") (pin "2") (pinfunction "2_2") (pintype "passive"))
      (node (ref "Q17") (pin "1") (pinfunction "A_1") (pintype "passive"))
    )
    (net (code "11") (name "/i9") (class "Default")
      (node (ref "30") (pin "2") (pinfunction "2_2") (pintype "passive"))
      (node (ref "Q18") (pin "1") (pinfunction "A_1") (pintype "passive"))
    )
    (net (code "12") (name "/i10") (class "Default")
      (node (ref "31") (pin "2") (pinfunction "2_2") (pintype "passive"))
      (node (ref "Q19") (pin "1") (pinfunction "A_1") (pintype "passive"))
    )
    (net (code "13") (name "/i11") (class "Default")
      (node (ref "32") (pin "2") (pinfunction "2_2") (pintype "passive"))
      (node (ref "Q20") (pin "1") (pinfunction "A_1") (pintype "passive"))
    )
    (net (code "14") (name "/i12") (class "Default")
      (node (ref "33") (pin "2") (pinfunction "2_2") (pintype "passive"))
      (node (ref "Q21") (pin "1") (pinfunction "A_1") (pintype "passive"))
    )
    (net (code "15") (name "/i13") (class "Default")
      (node (ref "34") (pin "2") (pinfunction "2_2") (pintype "passive"))
      (node (ref "Q22") (pin "1") (pinfunction "A_1") (pintype "passive"))
    )
    (net (code "16") (name "/i14") (class "Default")
      (node (ref "35") (pin "2") (pinfunction "2_2") (pintype "passive"))
      (node (ref "Q23") (pin "1") (pinfunction "A_1") (pintype "passive"))
    )
    (net (code "17") (name "/i15") (class "Default")
      (node (ref "13") (pin "2") (pinfunction "2_2") (pintype "passive"))
      (node (ref "Q1") (pin "1") (pinfunction "A_1") (pintype "passive"))
    )
    (net (code "18") (name "/i16") (class "Default")
      (node (ref "1") (pin "2") (pinfunction "2_2") (pintype "passive"))
      (node (ref "Q2") (pin "1") (pinfunction "A_1") (pintype "passive"))
    )
    (net (code "19") (name "/i17") (class "Default")
      (node (ref "2") (pin "2") (pinfunction "2_2") (pintype "passive"))
      (node (ref "Q3") (pin "1") (pinfunction "A_1") (pintype "passive"))
    )
    (net (code "20") (name "/i18") (class "Default")
      (node (ref "3") (pin "2") (pinfunction "2_2") (pintype "passive"))
      (node (ref "Q4") (pin "1") (pinfunction "A_1") (pintype "passive"))
    )
    (net (code "21") (name "/i19") (class "Default")
      (node (ref "4") (pin "2") (pinfunction "2_2") (pintype "passive"))
      (node (ref "Q5") (pin "1") (pinfunction "A_1") (pintype "passive"))
    )
    (net (code "22") (name "/i20") (class "Default")
      (node (ref "5") (pin "2") (pinfunction "2_2") (pintype "passive"))
      (node (ref "Q6") (pin "1") (pinfunction "A_1") (pintype "passive"))
    )
    (net (code "23") (name "/i21") (class "Default")
      (node (ref "6") (pin "2") (pinfunction "2_2") (pintype "passive"))
      (node (ref "Q7") (pin "1") (pinfunction "A_1") (pintype "passive"))
    )
    (net (code "24") (name "/i22") (class "Default")
      (node (ref "41") (pin "2") (pinfunction "2_2") (pintype "passive"))
      (node (ref "Q24") (pin "1") (pinfunction "A_1") (pintype "passive"))
    )
    (net (code "25") (name "/i23") (class "Default")
      (node (ref "42") (pin "2") (pinfunction "2_2") (pintype "passive"))
      (node (ref "Q25") (pin "1") (pinfunction "A_1") (pintype "passive"))
    )
    (net (code "26") (name "/i24") (class "Default")
      (node (ref "36") (pin "2") (pinfunction "2_2") (pintype "passive"))
      (node (ref "Q26") (pin "1") (pinfunction "A_1") (pintype "passive"))
    )
    (net (code "27") (name "/i25") (class "Default")
      (node (ref "37") (pin "2") (pinfunction "2_2") (pintype "passive"))
      (node (ref "Q27") (pin "1") (pinfunction "A_1") (pintype "passive"))
    )
    (net (code "28") (name "/i26") (class "Default")
      (node (ref "38") (pin "2") (pinfunction "2_2") (pintype "passive"))
      (node (ref "Q28") (pin "1") (pinfunction "A_1") (pintype "passive"))
    )
    (net (code "29") (name "/i27") (class "Default")
      (node (ref "39") (pin "2") (pinfunction "2_2") (pintype "passive"))
      (node (ref "Q29") (pin "1") (pinfunction "A_1") (pintype "passive"))
    )
    (net (code "30") (name "/i28") (class "Default")
      (node (ref "40") (pin "2") (pinfunction "2_2") (pintype "passive"))
      (node (ref "Q30") (pin "1") (pinfunction "A_1") (pintype "passive"))
    )
    (net (code "31") (name "/r1") (class "Default")
      (node (ref "CR1") (pin "2") (pinfunction "12_2") (pintype "passive"))
      (node (ref "Q16") (pin "16") (pinfunction "16_16") (pintype "passive"))
    )
    (net (code "32") (name "/r2") (class "Default")
      (node (ref "CR2") (pin "2") (pinfunction "12_2") (pintype "passive"))
      (node (ref "Q16") (pin "15") (pinfunction "15_15") (pintype "passive"))
    )
    (net (code "33") (name "/r3") (class "Default")
      (node (ref "CR3") (pin "2") (pinfunction "12_2") (pintype "passive"))
      (node (ref "Q16") (pin "14") (pinfunction "14_14") (pintype "passive"))
    )
    (net (code "34") (name "/r4") (class "Default")
      (node (ref "CR4") (pin "2") (pinfunction "12_2") (pintype "passive"))
      (node (ref "Q16") (pin "13") (pinfunction "13_13") (pintype "passive"))
    )
    (net (code "35") (name "/r5") (class "Default")
      (node (ref "CR5") (pin "2") (pinfunction "12_2") (pintype "passive"))
      (node (ref "Q16") (pin "12") (pinfunction "12_12") (pintype "passive"))
    )
    (net (code "36") (name "/r6") (class "Default")
      (node (ref "CR6") (pin "2") (pinfunction "12_2") (pintype "passive"))
      (node (ref "Q16") (pin "11") (pinfunction "11_11") (pintype "passive"))
    )
    (net (code "37") (name "/r7") (class "Default")
      (node (ref "CR7") (pin "2") (pinfunction "12_2") (pintype "passive"))
      (node (ref "Q16") (pin "10") (pinfunction "10_10") (pintype "passive"))
    )
    (net (code "38") (name "/r8") (class "Default")
      (node (ref "CR8") (pin "2") (pinfunction "12_2") (pintype "passive"))
      (node (ref "Q31") (pin "16") (pinfunction "16_16") (pintype "passive"))
    )
    (net (code "39") (name "/r9") (class "Default")
      (node (ref "CR9") (pin "2") (pinfunction "12_2") (pintype "passive"))
      (node (ref "Q31") (pin "15") (pinfunction "15_15") (pintype "passive"))
    )
    (net (code "40") (name "/r10") (class "Default")
      (node (ref "CR10") (pin "2") (pinfunction "12_2") (pintype "passive"))
      (node (ref "Q31") (pin "14") (pinfunction "14_14") (pintype "passive"))
    )
    (net (code "41") (name "/r11") (class "Default")
      (node (ref "CR11") (pin "2") (pinfunction "12_2") (pintype "passive"))
      (node (ref "Q31") (pin "13") (pinfunction "13_13") (pintype "passive"))
    )
    (net (code "42") (name "/r12") (class "Default")
      (node (ref "CR12") (pin "2") (pinfunction "12_2") (pintype "passive"))
      (node (ref "Q31") (pin "12") (pinfunction "12_12") (pintype "passive"))
    )
    (net (code "43") (name "/r13") (class "Default")
      (node (ref "CR13") (pin "2") (pinfunction "12_2") (pintype "passive"))
      (node (ref "Q31") (pin "11") (pinfunction "11_11") (pintype "passive"))
    )
    (net (code "44") (name "/r14") (class "Default")
      (node (ref "CR14") (pin "2") (pinfunction "12_2") (pintype "passive"))
      (node (ref "Q31") (pin "10") (pinfunction "10_10") (pintype "passive"))
    )
    (net (code "45") (name "/r15") (class "Default")
      (node (ref "CR15") (pin "2") (pinfunction "12_2") (pintype "passive"))
      (node (ref "Q15") (pin "16") (pinfunction "16_16") (pintype "passive"))
    )
    (net (code "46") (name "/r16") (class "Default")
      (node (ref "CR16") (pin "2") (pinfunction "12_2") (pintype "passive"))
      (node (ref "Q15") (pin "15") (pinfunction "15_15") (pintype "passive"))
    )
    (net (code "47") (name "/r17") (class "Default")
      (node (ref "CR17") (pin "2") (pinfunction "12_2") (pintype "passive"))
      (node (ref "Q15") (pin "14") (pinfunction "14_14") (pintype "passive"))
    )
    (net (code "48") (name "/r18") (class "Default")
      (node (ref "CR18") (pin "2") (pinfunction "12_2") (pintype "passive"))
      (node (ref "Q15") (pin "13") (pinfunction "13_13") (pintype "passive"))
    )
    (net (code "49") (name "/r19") (class "Default")
      (node (ref "CR19") (pin "2") (pinfunction "12_2") (pintype "passive"))
      (node (ref "Q15") (pin "12") (pinfunction "12_12") (pintype "passive"))
    )
    (net (code "50") (name "/r20") (class "Default")
      (node (ref "CR20") (pin "2") (pinfunction "12_2") (pintype "passive"))
      (node (ref "Q15") (pin "11") (pinfunction "11_11") (pintype "passive"))
    )
    (net (code "51") (name "/r21") (class "Default")
      (node (ref "CR21") (pin "2") (pinfunction "12_2") (pintype "passive"))
      (node (ref "Q15") (pin "10") (pinfunction "10_10") (pintype "passive"))
    )
    (net (code "52") (name "/r22") (class "Default")
      (node (ref "CR22") (pin "2") (pinfunction "12_2") (pintype "passive"))
      (node (ref "Q32") (pin "16") (pinfunction "16_16") (pintype "passive"))
    )
    (net (code "53") (name "/r23") (class "Default")
      (node (ref "CR23") (pin "2") (pinfunction "12_2") (pintype "passive"))
      (node (ref "Q32") (pin "15") (pinfunction "15_15") (pintype "passive"))
    )
    (net (code "54") (name "/r24") (class "Default")
      (node (ref "CR24") (pin "2") (pinfunction "12_2") (pintype "passive"))
      (node (ref "Q32") (pin "14") (pinfunction "14_14") (pintype "passive"))
    )
    (net (code "55") (name "/r25") (class "Default")
      (node (ref "CR25") (pin "2") (pinfunction "12_2") (pintype "passive"))
      (node (ref "Q32") (pin "13") (pinfunction "13_13") (pintype "passive"))
    )
    (net (code "56") (name "/r26") (class "Default")
      (node (ref "CR26") (pin "2") (pinfunction "12_2") (pintype "passive"))
      (node (ref "Q32") (pin "12") (pinfunction "12_12") (pintype "passive"))
    )
    (net (code "57") (name "/r27") (class "Default")
      (node (ref "CR27") (pin "2") (pinfunction "12_2") (pintype "passive"))
      (node (ref "Q32") (pin "11") (pinfunction "11_11") (pintype "passive"))
    )
    (net (code "58") (name "/r28") (class "Default")
      (node (ref "CR28") (pin "2") (pinfunction "12_2") (pintype "passive"))
      (node (ref "Q32") (pin "10") (pinfunction "10_10") (pintype "passive"))
    )
    (net (code "59") (name "GND") (class "Default")
      (node (ref "1") (pin "1") (pinfunction "1_1") (pintype "passive"))
      (node (ref "10") (pin "1") (pinfunction "1_1") (pintype "passive"))
      (node (ref "11") (pin "1") (pinfunction "1_1") (pintype "passive"))
      (node (ref "12") (pin "1") (pinfunction "1_1") (pintype "passive"))
      (node (ref "13") (pin "1") (pinfunction "1_1") (pintype "passive"))
      (node (ref "14") (pin "1") (pinfunction "1_1") (pintype "passive"))
      (node (ref "15") (pin "1") (pinfunction "1_1") (pintype "passive"))
      (node (ref "16") (pin "1") (pinfunction "1_1") (pintype "passive"))
      (node (ref "17") (pin "1") (pinfunction "1_1") (pintype "passive"))
      (node (ref "18") (pin "1") (pinfunction "1_1") (pintype "passive"))
      (node (ref "19") (pin "1") (pinfunction "1_1") (pintype "passive"))
      (node (ref "2") (pin "1") (pinfunction "1_1") (pintype "passive"))
      (node (ref "20") (pin "1") (pinfunction "1_1") (pintype "passive"))
      (node (ref "21") (pin "1") (pinfunction "1_1") (pintype "passive"))
      (node (ref "22") (pin "1") (pinfunction "1_1") (pintype "passive"))
      (node (ref "23") (pin "1") (pinfunction "1_1") (pintype "passive"))
      (node (ref "24") (pin "1") (pinfunction "1_1") (pintype "passive"))
      (node (ref "25") (pin "1") (pinfunction "1_1") (pintype "passive"))
      (node (ref "26") (pin "1") (pinfunction "1_1") (pintype "passive"))
      (node (ref "27") (pin "1") (pinfunction "1_1") (pintype "passive"))
      (node (ref "28") (pin "1") (pinfunction "1_1") (pintype "passive"))
      (node (ref "29") (pin "1") (pinfunction "1_1") (pintype "passive"))
      (node (ref "3") (pin "1") (pinfunction "1_1") (pintype "passive"))
      (node (ref "30") (pin "1") (pinfunction "1_1") (pintype "passive"))
      (node (ref "31") (pin "1") (pinfunction "1_1") (pintype "passive"))
      (node (ref "32") (pin "1") (pinfunction "1_1") (pintype "passive"))
      (node (ref "33") (pin "1") (pinfunction "1_1") (pintype "passive"))
      (node (ref "34") (pin "1") (pinfunction "1_1") (pintype "passive"))
      (node (ref "35") (pin "1") (pinfunction "1_1") (pintype "passive"))
      (node (ref "36") (pin "1") (pinfunction "1_1") (pintype "passive"))
      (node (ref "37") (pin "1") (pinfunction "1_1") (pintype "passive"))
      (node (ref "38") (pin "1") (pinfunction "1_1") (pintype "passive"))
      (node (ref "39") (pin "1") (pinfunction "1_1") (pintype "passive"))
      (node (ref "4") (pin "1") (pinfunction "1_1") (pintype "passive"))
      (node (ref "40") (pin "1") (pinfunction "1_1") (pintype "passive"))
      (node (ref "41") (pin "1") (pinfunction "1_1") (pintype "passive"))
      (node (ref "42") (pin "1") (pinfunction "1_1") (pintype "passive"))
      (node (ref "43") (pin "1") (pinfunction "1_1") (pintype "passive"))
      (node (ref "44") (pin "1") (pinfunction "1_1") (pintype "passive"))
      (node (ref "45") (pin "1") (pinfunction "1_1") (pintype "passive"))
      (node (ref "46") (pin "1") (pinfunction "1_1") (pintype "passive"))
      (node (ref "47") (pin "1") (pinfunction "1_1") (pintype "passive"))
      (node (ref "48") (pin "1") (pinfunction "1_1") (pintype "passive"))
      (node (ref "49") (pin "1") (pinfunction "1_1") (pintype "passive"))
      (node (ref "5") (pin "1") (pinfunction "1_1") (pintype "passive"))
      (node (ref "50") (pin "1") (pinfunction "1_1") (pintype "passive"))
      (node (ref "51") (pin "1") (pinfunction "1_1") (pintype "passive"))
      (node (ref "52") (pin "1") (pinfunction "1_1") (pintype "passive"))
      (node (ref "53") (pin "1") (pinfunction "1_1") (pintype "passive"))
      (node (ref "54") (pin "1") (pinfunction "1_1") (pintype "passive"))
      (node (ref "55") (pin "1") (pinfunction "1_1") (pintype "passive"))
      (node (ref "56") (pin "1") (pinfunction "1_1") (pintype "passive"))
      (node (ref "6") (pin "1") (pinfunction "1_1") (pintype "passive"))
      (node (ref "7") (pin "1") (pinfunction "1_1") (pintype "passive"))
      (node (ref "8") (pin "1") (pinfunction "1_1") (pintype "passive"))
      (node (ref "9") (pin "1") (pinfunction "1_1") (pintype "passive"))
    )
    (net (code "60") (name "Net-(15-Pad2)") (class "Default")
      (node (ref "15") (pin "2") (pinfunction "2_2") (pintype "passive"))
      (node (ref "Q2") (pin "2") (pinfunction "C_2") (pintype "passive"))
    )
    (net (code "61") (name "Net-(16-Pad2)") (class "Default")
      (node (ref "16") (pin "2") (pinfunction "2_2") (pintype "passive"))
      (node (ref "Q3") (pin "2") (pinfunction "C_2") (pintype "passive"))
    )
    (net (code "62") (name "Net-(17-Pad2)") (class "Default")
      (node (ref "17") (pin "2") (pinfunction "2_2") (pintype "passive"))
      (node (ref "Q4") (pin "2") (pinfunction "C_2") (pintype "passive"))
    )
    (net (code "63") (name "Net-(18-Pad2)") (class "Default")
      (node (ref "18") (pin "2") (pinfunction "2_2") (pintype "passive"))
      (node (ref "Q5") (pin "2") (pinfunction "C_2") (pintype "passive"))
    )
    (net (code "64") (name "Net-(19-Pad2)") (class "Default")
      (node (ref "19") (pin "2") (pinfunction "2_2") (pintype "passive"))
      (node (ref "Q6") (pin "2") (pinfunction "C_2") (pintype "passive"))
    )
    (net (code "65") (name "Net-(20-Pad2)") (class "Default")
      (node (ref "20") (pin "2") (pinfunction "2_2") (pintype "passive"))
      (node (ref "Q7") (pin "2") (pinfunction "C_2") (pintype "passive"))
    )
    (net (code "66") (name "Net-(21-Pad2)") (class "Default")
      (node (ref "21") (pin "2") (pinfunction "2_2") (pintype "passive"))
      (node (ref "Q9") (pin "2") (pinfunction "C_2") (pintype "passive"))
    )
    (net (code "67") (name "Net-(22-Pad2)") (class "Default")
      (node (ref "22") (pin "2") (pinfunction "2_2") (pintype "passive"))
      (node (ref "Q10") (pin "2") (pinfunction "C_2") (pintype "passive"))
    )
    (net (code "68") (name "Net-(23-Pad2)") (class "Default")
      (node (ref "23") (pin "2") (pinfunction "2_2") (pintype "passive"))
      (node (ref "Q11") (pin "2") (pinfunction "C_2") (pintype "passive"))
    )
    (net (code "69") (name "Net-(24-Pad2)") (class "Default")
      (node (ref "24") (pin "2") (pinfunction "2_2") (pintype "passive"))
      (node (ref "Q12") (pin "2") (pinfunction "C_2") (pintype "passive"))
    )
    (net (code "70") (name "Net-(25-Pad2)") (class "Default")
      (node (ref "25") (pin "2") (pinfunction "2_2") (pintype "passive"))
      (node (ref "Q13") (pin "2") (pinfunction "C_2") (pintype "passive"))
    )
    (net (code "71") (name "Net-(26-Pad2)") (class "Default")
      (node (ref "26") (pin "2") (pinfunction "2_2") (pintype "passive"))
      (node (ref "Q14") (pin "2") (pinfunction "C_2") (pintype "passive"))
    )
    (net (code "72") (name "Net-(27-Pad2)") (class "Default")
      (node (ref "27") (pin "2") (pinfunction "2_2") (pintype "passive"))
      (node (ref "Q1") (pin "2") (pinfunction "C_2") (pintype "passive"))
    )
    (net (code "73") (name "Net-(28-Pad2)") (class "Default")
      (node (ref "28") (pin "2") (pinfunction "2_2") (pintype "passive"))
      (node (ref "Q8") (pin "2") (pinfunction "C_2") (pintype "passive"))
    )
    (net (code "74") (name "Net-(43-Pad2)") (class "Default")
      (node (ref "43") (pin "2") (pinfunction "2_2") (pintype "passive"))
      (node (ref "Q17") (pin "2") (pinfunction "C_2") (pintype "passive"))
    )
    (net (code "75") (name "Net-(44-Pad2)") (class "Default")
      (node (ref "44") (pin "2") (pinfunction "2_2") (pintype "passive"))
      (node (ref "Q18") (pin "2") (pinfunction "C_2") (pintype "passive"))
    )
    (net (code "76") (name "Net-(45-Pad2)") (class "Default")
      (node (ref "45") (pin "2") (pinfunction "2_2") (pintype "passive"))
      (node (ref "Q19") (pin "2") (pinfunction "C_2") (pintype "passive"))
    )
    (net (code "77") (name "Net-(46-Pad2)") (class "Default")
      (node (ref "46") (pin "2") (pinfunction "2_2") (pintype "passive"))
      (node (ref "Q20") (pin "2") (pinfunction "C_2") (pintype "passive"))
    )
    (net (code "78") (name "Net-(47-Pad2)") (class "Default")
      (node (ref "47") (pin "2") (pinfunction "2_2") (pintype "passive"))
      (node (ref "Q21") (pin "2") (pinfunction "C_2") (pintype "passive"))
    )
    (net (code "79") (name "Net-(48-Pad2)") (class "Default")
      (node (ref "48") (pin "2") (pinfunction "2_2") (pintype "passive"))
      (node (ref "Q22") (pin "2") (pinfunction "C_2") (pintype "passive"))
    )
    (net (code "80") (name "Net-(49-Pad2)") (class "Default")
      (node (ref "49") (pin "2") (pinfunction "2_2") (pintype "passive"))
      (node (ref "Q23") (pin "2") (pinfunction "C_2") (pintype "passive"))
    )
    (net (code "81") (name "Net-(50-Pad2)") (class "Default")
      (node (ref "50") (pin "2") (pinfunction "2_2") (pintype "passive"))
      (node (ref "Q26") (pin "2") (pinfunction "C_2") (pintype "passive"))
    )
    (net (code "82") (name "Net-(51-Pad2)") (class "Default")
      (node (ref "51") (pin "2") (pinfunction "2_2") (pintype "passive"))
      (node (ref "Q27") (pin "2") (pinfunction "C_2") (pintype "passive"))
    )
    (net (code "83") (name "Net-(52-Pad2)") (class "Default")
      (node (ref "52") (pin "2") (pinfunction "2_2") (pintype "passive"))
      (node (ref "Q28") (pin "2") (pinfunction "C_2") (pintype "passive"))
    )
    (net (code "84") (name "Net-(53-Pad2)") (class "Default")
      (node (ref "53") (pin "2") (pinfunction "2_2") (pintype "passive"))
      (node (ref "Q29") (pin "2") (pinfunction "C_2") (pintype "passive"))
    )
    (net (code "85") (name "Net-(54-Pad2)") (class "Default")
      (node (ref "54") (pin "2") (pinfunction "2_2") (pintype "passive"))
      (node (ref "Q30") (pin "2") (pinfunction "C_2") (pintype "passive"))
    )
    (net (code "86") (name "Net-(55-Pad2)") (class "Default")
      (node (ref "55") (pin "2") (pinfunction "2_2") (pintype "passive"))
      (node (ref "Q24") (pin "2") (pinfunction "C_2") (pintype "passive"))
    )
    (net (code "87") (name "Net-(56-Pad2)") (class "Default")
      (node (ref "56") (pin "2") (pinfunction "2_2") (pintype "passive"))
      (node (ref "Q25") (pin "2") (pinfunction "C_2") (pintype "passive"))
    )
    (net (code "88") (name "Net-(Q1-E)") (class "Default")
      (node (ref "Q1") (pin "3") (pinfunction "E_3") (pintype "passive"))
      (node (ref "Q15") (pin "1") (pinfunction "1_1") (pintype "passive"))
    )
    (net (code "89") (name "Net-(Q2-E)") (class "Default")
      (node (ref "Q15") (pin "2") (pinfunction "2_2") (pintype "passive"))
      (node (ref "Q2") (pin "3") (pinfunction "E_3") (pintype "passive"))
    )
    (net (code "90") (name "Net-(Q3-E)") (class "Default")
      (node (ref "Q15") (pin "3") (pinfunction "3_3") (pintype "passive"))
      (node (ref "Q3") (pin "3") (pinfunction "E_3") (pintype "passive"))
    )
    (net (code "91") (name "Net-(Q4-E)") (class "Default")
      (node (ref "Q15") (pin "4") (pinfunction "4_4") (pintype "passive"))
      (node (ref "Q4") (pin "3") (pinfunction "E_3") (pintype "passive"))
    )
    (net (code "92") (name "Net-(Q5-E)") (class "Default")
      (node (ref "Q15") (pin "5") (pinfunction "5_5") (pintype "passive"))
      (node (ref "Q5") (pin "3") (pinfunction "E_3") (pintype "passive"))
    )
    (net (code "93") (name "Net-(Q6-E)") (class "Default")
      (node (ref "Q15") (pin "6") (pinfunction "6_6") (pintype "passive"))
      (node (ref "Q6") (pin "3") (pinfunction "E_3") (pintype "passive"))
    )
    (net (code "94") (name "Net-(Q7-E)") (class "Default")
      (node (ref "Q15") (pin "7") (pinfunction "7_7") (pintype "passive"))
      (node (ref "Q7") (pin "3") (pinfunction "E_3") (pintype "passive"))
    )
    (net (code "95") (name "Net-(Q8-E)") (class "Default")
      (node (ref "Q16") (pin "1") (pinfunction "1_1") (pintype "passive"))
      (node (ref "Q8") (pin "3") (pinfunction "E_3") (pintype "passive"))
    )
    (net (code "96") (name "Net-(Q9-E)") (class "Default")
      (node (ref "Q16") (pin "2") (pinfunction "2_2") (pintype "passive"))
      (node (ref "Q9") (pin "3") (pinfunction "E_3") (pintype "passive"))
    )
    (net (code "97") (name "Net-(Q10-E)") (class "Default")
      (node (ref "Q10") (pin "3") (pinfunction "E_3") (pintype "passive"))
      (node (ref "Q16") (pin "3") (pinfunction "3_3") (pintype "passive"))
    )
    (net (code "98") (name "Net-(Q11-E)") (class "Default")
      (node (ref "Q11") (pin "3") (pinfunction "E_3") (pintype "passive"))
      (node (ref "Q16") (pin "4") (pinfunction "4_4") (pintype "passive"))
    )
    (net (code "99") (name "Net-(Q12-E)") (class "Default")
      (node (ref "Q12") (pin "3") (pinfunction "E_3") (pintype "passive"))
      (node (ref "Q16") (pin "5") (pinfunction "5_5") (pintype "passive"))
    )
    (net (code "100") (name "Net-(Q13-E)") (class "Default")
      (node (ref "Q13") (pin "3") (pinfunction "E_3") (pintype "passive"))
      (node (ref "Q16") (pin "6") (pinfunction "6_6") (pintype "passive"))
    )
    (net (code "101") (name "Net-(Q14-E)") (class "Default")
      (node (ref "Q14") (pin "3") (pinfunction "E_3") (pintype "passive"))
      (node (ref "Q16") (pin "7") (pinfunction "7_7") (pintype "passive"))
    )
    (net (code "102") (name "Net-(Q17-E)") (class "Default")
      (node (ref "Q17") (pin "3") (pinfunction "E_3") (pintype "passive"))
      (node (ref "Q31") (pin "1") (pinfunction "1_1") (pintype "passive"))
    )
    (net (code "103") (name "Net-(Q18-E)") (class "Default")
      (node (ref "Q18") (pin "3") (pinfunction "E_3") (pintype "passive"))
      (node (ref "Q31") (pin "2") (pinfunction "2_2") (pintype "passive"))
    )
    (net (code "104") (name "Net-(Q19-E)") (class "Default")
      (node (ref "Q19") (pin "3") (pinfunction "E_3") (pintype "passive"))
      (node (ref "Q31") (pin "3") (pinfunction "3_3") (pintype "passive"))
    )
    (net (code "105") (name "Net-(Q20-E)") (class "Default")
      (node (ref "Q20") (pin "3") (pinfunction "E_3") (pintype "passive"))
      (node (ref "Q31") (pin "4") (pinfunction "4_4") (pintype "passive"))
    )
    (net (code "106") (name "Net-(Q21-E)") (class "Default")
      (node (ref "Q21") (pin "3") (pinfunction "E_3") (pintype "passive"))
      (node (ref "Q31") (pin "5") (pinfunction "5_5") (pintype "passive"))
    )
    (net (code "107") (name "Net-(Q22-E)") (class "Default")
      (node (ref "Q22") (pin "3") (pinfunction "E_3") (pintype "passive"))
      (node (ref "Q31") (pin "6") (pinfunction "6_6") (pintype "passive"))
    )
    (net (code "108") (name "Net-(Q23-E)") (class "Default")
      (node (ref "Q23") (pin "3") (pinfunction "E_3") (pintype "passive"))
      (node (ref "Q31") (pin "7") (pinfunction "7_7") (pintype "passive"))
    )
    (net (code "109") (name "Net-(Q24-E)") (class "Default")
      (node (ref "Q24") (pin "3") (pinfunction "E_3") (pintype "passive"))
      (node (ref "Q32") (pin "1") (pinfunction "1_1") (pintype "passive"))
    )
    (net (code "110") (name "Net-(Q25-E)") (class "Default")
      (node (ref "Q25") (pin "3") (pinfunction "E_3") (pintype "passive"))
      (node (ref "Q32") (pin "2") (pinfunction "2_2") (pintype "passive"))
    )
    (net (code "111") (name "Net-(Q26-E)") (class "Default")
      (node (ref "Q26") (pin "3") (pinfunction "E_3") (pintype "passive"))
      (node (ref "Q32") (pin "3") (pinfunction "3_3") (pintype "passive"))
    )
    (net (code "112") (name "Net-(Q27-E)") (class "Default")
      (node (ref "Q27") (pin "3") (pinfunction "E_3") (pintype "passive"))
      (node (ref "Q32") (pin "4") (pinfunction "4_4") (pintype "passive"))
    )
    (net (code "113") (name "Net-(Q28-E)") (class "Default")
      (node (ref "Q28") (pin "3") (pinfunction "E_3") (pintype "passive"))
      (node (ref "Q32") (pin "5") (pinfunction "5_5") (pintype "passive"))
    )
    (net (code "114") (name "Net-(Q29-E)") (class "Default")
      (node (ref "Q29") (pin "3") (pinfunction "E_3") (pintype "passive"))
      (node (ref "Q32") (pin "6") (pinfunction "6_6") (pintype "passive"))
    )
    (net (code "115") (name "Net-(Q30-E)") (class "Default")
      (node (ref "Q30") (pin "3") (pinfunction "E_3") (pintype "passive"))
      (node (ref "Q32") (pin "7") (pinfunction "7_7") (pintype "passive"))
    )
    (net (code "116") (name "pwr gnd") (class "Default")
      (node (ref "Q15") (pin "8") (pinfunction "8_8") (pintype "passive"))
      (node (ref "Q16") (pin "8") (pinfunction "8_8") (pintype "passive"))
      (node (ref "Q31") (pin "8") (pinfunction "8_8") (pintype "passive"))
      (node (ref "Q32") (pin "8") (pinfunction "8_8") (pintype "passive"))
    )
    (net (code "117") (name "unconnected-(Q15-Pad9)") (class "Default")
      (node (ref "Q15") (pin "9") (pinfunction "9_9") (pintype "passive"))
    )
    (net (code "118") (name "unconnected-(Q16-Pad9)") (class "Default")
      (node (ref "Q16") (pin "9") (pinfunction "9_9") (pintype "passive"))
    )
    (net (code "119") (name "unconnected-(Q31-Pad9)") (class "Default")
      (node (ref "Q31") (pin "9") (pinfunction "9_9") (pintype "passive"))
    )
    (net (code "120") (name "unconnected-(Q32-Pad9)") (class "Default")
      (node (ref "Q32") (pin "9") (pinfunction "9_9") (pintype "passive"))
    )
  )
)
